# Spannungsteiler_high.net
KiCad netlist of a schematic drawn in Altium Designer
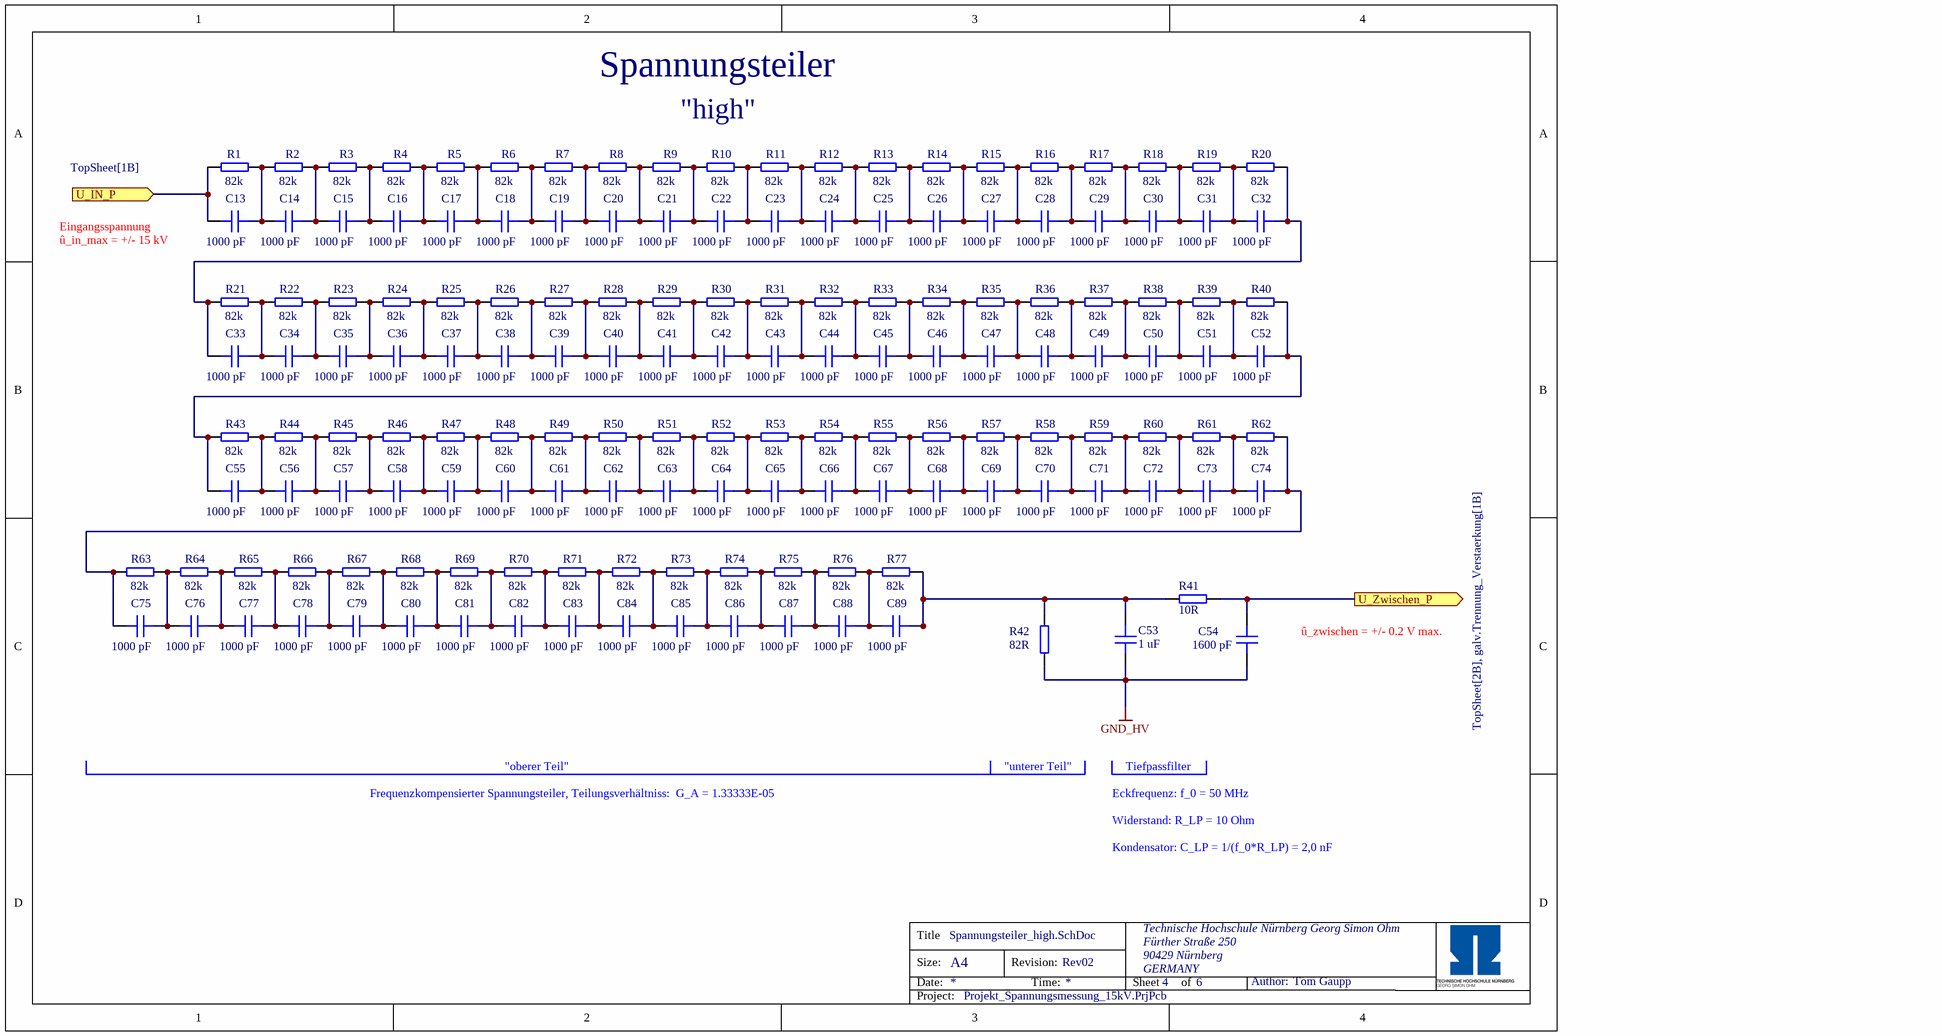
[diagram p0: Spannungsteiler_high.SchDoc]

(export (version "E")
  (design (tool "Eeschema 10.0.6"))
  (components
    (comp (ref "C13")
      (value "1000 pF")
      (footprint "C_1206")
      (description "Capacitor 1206, 200VDC, 1000pF, C0G, 5%")
      (fields
        (field (name "MANUFACTURER") "KEMET")
        (field (name "MANUFACTURER PART NUMBER") "C1206C102J2GACTU")
        (field (name "CREATED FROM") "TGaupp")
      )
      (libsource (lib "user") (part "Capacitor"))
    )
    (comp (ref "C14")
      (value "1000 pF")
      (footprint "C_1206")
      (description "Capacitor 1206, 200VDC, 1000pF, C0G, 5%")
      (fields
        (field (name "MANUFACTURER") "KEMET")
        (field (name "MANUFACTURER PART NUMBER") "C1206C102J2GACTU")
        (field (name "CREATED FROM") "TGaupp")
      )
      (libsource (lib "user") (part "Capacitor"))
    )
    (comp (ref "C15")
      (value "1000 pF")
      (footprint "C_1206")
      (description "Capacitor 1206, 200VDC, 1000pF, C0G, 5%")
      (fields
        (field (name "MANUFACTURER") "KEMET")
        (field (name "MANUFACTURER PART NUMBER") "C1206C102J2GACTU")
        (field (name "CREATED FROM") "TGaupp")
      )
      (libsource (lib "user") (part "Capacitor"))
    )
    (comp (ref "C16")
      (value "1000 pF")
      (footprint "C_1206")
      (description "Capacitor 1206, 200VDC, 1000pF, C0G, 5%")
      (fields
        (field (name "MANUFACTURER") "KEMET")
        (field (name "MANUFACTURER PART NUMBER") "C1206C102J2GACTU")
        (field (name "CREATED FROM") "TGaupp")
      )
      (libsource (lib "user") (part "Capacitor"))
    )
    (comp (ref "C17")
      (value "1000 pF")
      (footprint "C_1206")
      (description "Capacitor 1206, 200VDC, 1000pF, C0G, 5%")
      (fields
        (field (name "MANUFACTURER") "KEMET")
        (field (name "MANUFACTURER PART NUMBER") "C1206C102J2GACTU")
        (field (name "CREATED FROM") "TGaupp")
      )
      (libsource (lib "user") (part "Capacitor"))
    )
    (comp (ref "C18")
      (value "1000 pF")
      (footprint "C_1206")
      (description "Capacitor 1206, 200VDC, 1000pF, C0G, 5%")
      (fields
        (field (name "MANUFACTURER") "KEMET")
        (field (name "MANUFACTURER PART NUMBER") "C1206C102J2GACTU")
        (field (name "CREATED FROM") "TGaupp")
      )
      (libsource (lib "user") (part "Capacitor"))
    )
    (comp (ref "C19")
      (value "1000 pF")
      (footprint "C_1206")
      (description "Capacitor 1206, 200VDC, 1000pF, C0G, 5%")
      (fields
        (field (name "MANUFACTURER") "KEMET")
        (field (name "MANUFACTURER PART NUMBER") "C1206C102J2GACTU")
        (field (name "CREATED FROM") "TGaupp")
      )
      (libsource (lib "user") (part "Capacitor"))
    )
    (comp (ref "C20")
      (value "1000 pF")
      (footprint "C_1206")
      (description "Capacitor 1206, 200VDC, 1000pF, C0G, 5%")
      (fields
        (field (name "MANUFACTURER") "KEMET")
        (field (name "MANUFACTURER PART NUMBER") "C1206C102J2GACTU")
        (field (name "CREATED FROM") "TGaupp")
      )
      (libsource (lib "user") (part "Capacitor"))
    )
    (comp (ref "C21")
      (value "1000 pF")
      (footprint "C_1206")
      (description "Capacitor 1206, 200VDC, 1000pF, C0G, 5%")
      (fields
        (field (name "MANUFACTURER") "KEMET")
        (field (name "MANUFACTURER PART NUMBER") "C1206C102J2GACTU")
        (field (name "CREATED FROM") "TGaupp")
      )
      (libsource (lib "user") (part "Capacitor"))
    )
    (comp (ref "C22")
      (value "1000 pF")
      (footprint "C_1206")
      (description "Capacitor 1206, 200VDC, 1000pF, C0G, 5%")
      (fields
        (field (name "MANUFACTURER") "KEMET")
        (field (name "MANUFACTURER PART NUMBER") "C1206C102J2GACTU")
        (field (name "CREATED FROM") "TGaupp")
      )
      (libsource (lib "user") (part "Capacitor"))
    )
    (comp (ref "C23")
      (value "1000 pF")
      (footprint "C_1206")
      (description "Capacitor 1206, 200VDC, 1000pF, C0G, 5%")
      (fields
        (field (name "MANUFACTURER") "KEMET")
        (field (name "MANUFACTURER PART NUMBER") "C1206C102J2GACTU")
        (field (name "CREATED FROM") "TGaupp")
      )
      (libsource (lib "user") (part "Capacitor"))
    )
    (comp (ref "C24")
      (value "1000 pF")
      (footprint "C_1206")
      (description "Capacitor 1206, 200VDC, 1000pF, C0G, 5%")
      (fields
        (field (name "MANUFACTURER") "KEMET")
        (field (name "MANUFACTURER PART NUMBER") "C1206C102J2GACTU")
        (field (name "CREATED FROM") "TGaupp")
      )
      (libsource (lib "user") (part "Capacitor"))
    )
    (comp (ref "C25")
      (value "1000 pF")
      (footprint "C_1206")
      (description "Capacitor 1206, 200VDC, 1000pF, C0G, 5%")
      (fields
        (field (name "MANUFACTURER") "KEMET")
        (field (name "MANUFACTURER PART NUMBER") "C1206C102J2GACTU")
        (field (name "CREATED FROM") "TGaupp")
      )
      (libsource (lib "user") (part "Capacitor"))
    )
    (comp (ref "C26")
      (value "1000 pF")
      (footprint "C_1206")
      (description "Capacitor 1206, 200VDC, 1000pF, C0G, 5%")
      (fields
        (field (name "MANUFACTURER") "KEMET")
        (field (name "MANUFACTURER PART NUMBER") "C1206C102J2GACTU")
        (field (name "CREATED FROM") "TGaupp")
      )
      (libsource (lib "user") (part "Capacitor"))
    )
    (comp (ref "C27")
      (value "1000 pF")
      (footprint "C_1206")
      (description "Capacitor 1206, 200VDC, 1000pF, C0G, 5%")
      (fields
        (field (name "MANUFACTURER") "KEMET")
        (field (name "MANUFACTURER PART NUMBER") "C1206C102J2GACTU")
        (field (name "CREATED FROM") "TGaupp")
      )
      (libsource (lib "user") (part "Capacitor"))
    )
    (comp (ref "C28")
      (value "1000 pF")
      (footprint "C_1206")
      (description "Capacitor 1206, 200VDC, 1000pF, C0G, 5%")
      (fields
        (field (name "MANUFACTURER") "KEMET")
        (field (name "MANUFACTURER PART NUMBER") "C1206C102J2GACTU")
        (field (name "CREATED FROM") "TGaupp")
      )
      (libsource (lib "user") (part "Capacitor"))
    )
    (comp (ref "C29")
      (value "1000 pF")
      (footprint "C_1206")
      (description "Capacitor 1206, 200VDC, 1000pF, C0G, 5%")
      (fields
        (field (name "MANUFACTURER") "KEMET")
        (field (name "MANUFACTURER PART NUMBER") "C1206C102J2GACTU")
        (field (name "CREATED FROM") "TGaupp")
      )
      (libsource (lib "user") (part "Capacitor"))
    )
    (comp (ref "C30")
      (value "1000 pF")
      (footprint "C_1206")
      (description "Capacitor 1206, 200VDC, 1000pF, C0G, 5%")
      (fields
        (field (name "MANUFACTURER") "KEMET")
        (field (name "MANUFACTURER PART NUMBER") "C1206C102J2GACTU")
        (field (name "CREATED FROM") "TGaupp")
      )
      (libsource (lib "user") (part "Capacitor"))
    )
    (comp (ref "C31")
      (value "1000 pF")
      (footprint "C_1206")
      (description "Capacitor 1206, 200VDC, 1000pF, C0G, 5%")
      (fields
        (field (name "MANUFACTURER") "KEMET")
        (field (name "MANUFACTURER PART NUMBER") "C1206C102J2GACTU")
        (field (name "CREATED FROM") "TGaupp")
      )
      (libsource (lib "user") (part "Capacitor"))
    )
    (comp (ref "C32")
      (value "1000 pF")
      (footprint "C_1206")
      (description "Capacitor 1206, 200VDC, 1000pF, C0G, 5%")
      (fields
        (field (name "MANUFACTURER") "KEMET")
        (field (name "MANUFACTURER PART NUMBER") "C1206C102J2GACTU")
        (field (name "CREATED FROM") "TGaupp")
      )
      (libsource (lib "user") (part "Capacitor"))
    )
    (comp (ref "C33")
      (value "1000 pF")
      (footprint "C_1206")
      (description "Capacitor 1206, 200VDC, 1000pF, C0G, 5%")
      (fields
        (field (name "MANUFACTURER") "KEMET")
        (field (name "MANUFACTURER PART NUMBER") "C1206C102J2GACTU")
        (field (name "CREATED FROM") "TGaupp")
      )
      (libsource (lib "user") (part "Capacitor"))
    )
    (comp (ref "C34")
      (value "1000 pF")
      (footprint "C_1206")
      (description "Capacitor 1206, 200VDC, 1000pF, C0G, 5%")
      (fields
        (field (name "MANUFACTURER") "KEMET")
        (field (name "MANUFACTURER PART NUMBER") "C1206C102J2GACTU")
        (field (name "CREATED FROM") "TGaupp")
      )
      (libsource (lib "user") (part "Capacitor"))
    )
    (comp (ref "C35")
      (value "1000 pF")
      (footprint "C_1206")
      (description "Capacitor 1206, 200VDC, 1000pF, C0G, 5%")
      (fields
        (field (name "MANUFACTURER") "KEMET")
        (field (name "MANUFACTURER PART NUMBER") "C1206C102J2GACTU")
        (field (name "CREATED FROM") "TGaupp")
      )
      (libsource (lib "user") (part "Capacitor"))
    )
    (comp (ref "C36")
      (value "1000 pF")
      (footprint "C_1206")
      (description "Capacitor 1206, 200VDC, 1000pF, C0G, 5%")
      (fields
        (field (name "MANUFACTURER") "KEMET")
        (field (name "MANUFACTURER PART NUMBER") "C1206C102J2GACTU")
        (field (name "CREATED FROM") "TGaupp")
      )
      (libsource (lib "user") (part "Capacitor"))
    )
    (comp (ref "C37")
      (value "1000 pF")
      (footprint "C_1206")
      (description "Capacitor 1206, 200VDC, 1000pF, C0G, 5%")
      (fields
        (field (name "MANUFACTURER") "KEMET")
        (field (name "MANUFACTURER PART NUMBER") "C1206C102J2GACTU")
        (field (name "CREATED FROM") "TGaupp")
      )
      (libsource (lib "user") (part "Capacitor"))
    )
    (comp (ref "C38")
      (value "1000 pF")
      (footprint "C_1206")
      (description "Capacitor 1206, 200VDC, 1000pF, C0G, 5%")
      (fields
        (field (name "MANUFACTURER") "KEMET")
        (field (name "MANUFACTURER PART NUMBER") "C1206C102J2GACTU")
        (field (name "CREATED FROM") "TGaupp")
      )
      (libsource (lib "user") (part "Capacitor"))
    )
    (comp (ref "C39")
      (value "1000 pF")
      (footprint "C_1206")
      (description "Capacitor 1206, 200VDC, 1000pF, C0G, 5%")
      (fields
        (field (name "MANUFACTURER") "KEMET")
        (field (name "MANUFACTURER PART NUMBER") "C1206C102J2GACTU")
        (field (name "CREATED FROM") "TGaupp")
      )
      (libsource (lib "user") (part "Capacitor"))
    )
    (comp (ref "C40")
      (value "1000 pF")
      (footprint "C_1206")
      (description "Capacitor 1206, 200VDC, 1000pF, C0G, 5%")
      (fields
        (field (name "MANUFACTURER") "KEMET")
        (field (name "MANUFACTURER PART NUMBER") "C1206C102J2GACTU")
        (field (name "CREATED FROM") "TGaupp")
      )
      (libsource (lib "user") (part "Capacitor"))
    )
    (comp (ref "C41")
      (value "1000 pF")
      (footprint "C_1206")
      (description "Capacitor 1206, 200VDC, 1000pF, C0G, 5%")
      (fields
        (field (name "MANUFACTURER") "KEMET")
        (field (name "MANUFACTURER PART NUMBER") "C1206C102J2GACTU")
        (field (name "CREATED FROM") "TGaupp")
      )
      (libsource (lib "user") (part "Capacitor"))
    )
    (comp (ref "C42")
      (value "1000 pF")
      (footprint "C_1206")
      (description "Capacitor 1206, 200VDC, 1000pF, C0G, 5%")
      (fields
        (field (name "MANUFACTURER") "KEMET")
        (field (name "MANUFACTURER PART NUMBER") "C1206C102J2GACTU")
        (field (name "CREATED FROM") "TGaupp")
      )
      (libsource (lib "user") (part "Capacitor"))
    )
    (comp (ref "C43")
      (value "1000 pF")
      (footprint "C_1206")
      (description "Capacitor 1206, 200VDC, 1000pF, C0G, 5%")
      (fields
        (field (name "MANUFACTURER") "KEMET")
        (field (name "MANUFACTURER PART NUMBER") "C1206C102J2GACTU")
        (field (name "CREATED FROM") "TGaupp")
      )
      (libsource (lib "user") (part "Capacitor"))
    )
    (comp (ref "C44")
      (value "1000 pF")
      (footprint "C_1206")
      (description "Capacitor 1206, 200VDC, 1000pF, C0G, 5%")
      (fields
        (field (name "MANUFACTURER") "KEMET")
        (field (name "MANUFACTURER PART NUMBER") "C1206C102J2GACTU")
        (field (name "CREATED FROM") "TGaupp")
      )
      (libsource (lib "user") (part "Capacitor"))
    )
    (comp (ref "C45")
      (value "1000 pF")
      (footprint "C_1206")
      (description "Capacitor 1206, 200VDC, 1000pF, C0G, 5%")
      (fields
        (field (name "MANUFACTURER") "KEMET")
        (field (name "MANUFACTURER PART NUMBER") "C1206C102J2GACTU")
        (field (name "CREATED FROM") "TGaupp")
      )
      (libsource (lib "user") (part "Capacitor"))
    )
    (comp (ref "C46")
      (value "1000 pF")
      (footprint "C_1206")
      (description "Capacitor 1206, 200VDC, 1000pF, C0G, 5%")
      (fields
        (field (name "MANUFACTURER") "KEMET")
        (field (name "MANUFACTURER PART NUMBER") "C1206C102J2GACTU")
        (field (name "CREATED FROM") "TGaupp")
      )
      (libsource (lib "user") (part "Capacitor"))
    )
    (comp (ref "C47")
      (value "1000 pF")
      (footprint "C_1206")
      (description "Capacitor 1206, 200VDC, 1000pF, C0G, 5%")
      (fields
        (field (name "MANUFACTURER") "KEMET")
        (field (name "MANUFACTURER PART NUMBER") "C1206C102J2GACTU")
        (field (name "CREATED FROM") "TGaupp")
      )
      (libsource (lib "user") (part "Capacitor"))
    )
    (comp (ref "C48")
      (value "1000 pF")
      (footprint "C_1206")
      (description "Capacitor 1206, 200VDC, 1000pF, C0G, 5%")
      (fields
        (field (name "MANUFACTURER") "KEMET")
        (field (name "MANUFACTURER PART NUMBER") "C1206C102J2GACTU")
        (field (name "CREATED FROM") "TGaupp")
      )
      (libsource (lib "user") (part "Capacitor"))
    )
    (comp (ref "C49")
      (value "1000 pF")
      (footprint "C_1206")
      (description "Capacitor 1206, 200VDC, 1000pF, C0G, 5%")
      (fields
        (field (name "MANUFACTURER") "KEMET")
        (field (name "MANUFACTURER PART NUMBER") "C1206C102J2GACTU")
        (field (name "CREATED FROM") "TGaupp")
      )
      (libsource (lib "user") (part "Capacitor"))
    )
    (comp (ref "C50")
      (value "1000 pF")
      (footprint "C_1206")
      (description "Capacitor 1206, 200VDC, 1000pF, C0G, 5%")
      (fields
        (field (name "MANUFACTURER") "KEMET")
        (field (name "MANUFACTURER PART NUMBER") "C1206C102J2GACTU")
        (field (name "CREATED FROM") "TGaupp")
      )
      (libsource (lib "user") (part "Capacitor"))
    )
    (comp (ref "C51")
      (value "1000 pF")
      (footprint "C_1206")
      (description "Capacitor 1206, 200VDC, 1000pF, C0G, 5%")
      (fields
        (field (name "MANUFACTURER") "KEMET")
        (field (name "MANUFACTURER PART NUMBER") "C1206C102J2GACTU")
        (field (name "CREATED FROM") "TGaupp")
      )
      (libsource (lib "user") (part "Capacitor"))
    )
    (comp (ref "C52")
      (value "1000 pF")
      (footprint "C_1206")
      (description "Capacitor 1206, 200VDC, 1000pF, C0G, 5%")
      (fields
        (field (name "MANUFACTURER") "KEMET")
        (field (name "MANUFACTURER PART NUMBER") "C1206C102J2GACTU")
        (field (name "CREATED FROM") "TGaupp")
      )
      (libsource (lib "user") (part "Capacitor"))
    )
    (comp (ref "C53")
      (value "1 uF")
      (footprint "C_1206")
      (description "Capacitor 1206, 50V, 1uF, X7R, 5%")
      (fields
        (field (name "MANUFACTURER PART NUMBER") "C1206X105J5RACTU")
        (field (name "MANUFACTURER") "KEMET")
        (field (name "CREATED FROM") "TGaupp")
      )
      (libsource (lib "user") (part "Capacitor"))
    )
    (comp (ref "C54")
      (value "1600 pF")
      (footprint "C_1206")
      (description "Capacitor 1206, 25V, 1600pF, X8R, 10%")
      (fields
        (field (name "MANUFACTURER") "KEMET")
        (field (name "MANUFACTURER PART NUMBER") "C1206C162K3HACTU")
        (field (name "CREATED FROM") "TGaupp")
      )
      (libsource (lib "user") (part "Capacitor"))
    )
    (comp (ref "C55")
      (value "1000 pF")
      (footprint "C_1206")
      (description "Capacitor 1206, 200VDC, 1000pF, C0G, 5%")
      (fields
        (field (name "MANUFACTURER") "KEMET")
        (field (name "MANUFACTURER PART NUMBER") "C1206C102J2GACTU")
        (field (name "CREATED FROM") "TGaupp")
      )
      (libsource (lib "user") (part "Capacitor"))
    )
    (comp (ref "C56")
      (value "1000 pF")
      (footprint "C_1206")
      (description "Capacitor 1206, 200VDC, 1000pF, C0G, 5%")
      (fields
        (field (name "MANUFACTURER") "KEMET")
        (field (name "MANUFACTURER PART NUMBER") "C1206C102J2GACTU")
        (field (name "CREATED FROM") "TGaupp")
      )
      (libsource (lib "user") (part "Capacitor"))
    )
    (comp (ref "C57")
      (value "1000 pF")
      (footprint "C_1206")
      (description "Capacitor 1206, 200VDC, 1000pF, C0G, 5%")
      (fields
        (field (name "MANUFACTURER") "KEMET")
        (field (name "MANUFACTURER PART NUMBER") "C1206C102J2GACTU")
        (field (name "CREATED FROM") "TGaupp")
      )
      (libsource (lib "user") (part "Capacitor"))
    )
    (comp (ref "C58")
      (value "1000 pF")
      (footprint "C_1206")
      (description "Capacitor 1206, 200VDC, 1000pF, C0G, 5%")
      (fields
        (field (name "MANUFACTURER") "KEMET")
        (field (name "MANUFACTURER PART NUMBER") "C1206C102J2GACTU")
        (field (name "CREATED FROM") "TGaupp")
      )
      (libsource (lib "user") (part "Capacitor"))
    )
    (comp (ref "C59")
      (value "1000 pF")
      (footprint "C_1206")
      (description "Capacitor 1206, 200VDC, 1000pF, C0G, 5%")
      (fields
        (field (name "MANUFACTURER") "KEMET")
        (field (name "MANUFACTURER PART NUMBER") "C1206C102J2GACTU")
        (field (name "CREATED FROM") "TGaupp")
      )
      (libsource (lib "user") (part "Capacitor"))
    )
    (comp (ref "C60")
      (value "1000 pF")
      (footprint "C_1206")
      (description "Capacitor 1206, 200VDC, 1000pF, C0G, 5%")
      (fields
        (field (name "MANUFACTURER") "KEMET")
        (field (name "MANUFACTURER PART NUMBER") "C1206C102J2GACTU")
        (field (name "CREATED FROM") "TGaupp")
      )
      (libsource (lib "user") (part "Capacitor"))
    )
    (comp (ref "C61")
      (value "1000 pF")
      (footprint "C_1206")
      (description "Capacitor 1206, 200VDC, 1000pF, C0G, 5%")
      (fields
        (field (name "MANUFACTURER") "KEMET")
        (field (name "MANUFACTURER PART NUMBER") "C1206C102J2GACTU")
        (field (name "CREATED FROM") "TGaupp")
      )
      (libsource (lib "user") (part "Capacitor"))
    )
    (comp (ref "C62")
      (value "1000 pF")
      (footprint "C_1206")
      (description "Capacitor 1206, 200VDC, 1000pF, C0G, 5%")
      (fields
        (field (name "MANUFACTURER") "KEMET")
        (field (name "MANUFACTURER PART NUMBER") "C1206C102J2GACTU")
        (field (name "CREATED FROM") "TGaupp")
      )
      (libsource (lib "user") (part "Capacitor"))
    )
    (comp (ref "C63")
      (value "1000 pF")
      (footprint "C_1206")
      (description "Capacitor 1206, 200VDC, 1000pF, C0G, 5%")
      (fields
        (field (name "MANUFACTURER") "KEMET")
        (field (name "MANUFACTURER PART NUMBER") "C1206C102J2GACTU")
        (field (name "CREATED FROM") "TGaupp")
      )
      (libsource (lib "user") (part "Capacitor"))
    )
    (comp (ref "C64")
      (value "1000 pF")
      (footprint "C_1206")
      (description "Capacitor 1206, 200VDC, 1000pF, C0G, 5%")
      (fields
        (field (name "MANUFACTURER") "KEMET")
        (field (name "MANUFACTURER PART NUMBER") "C1206C102J2GACTU")
        (field (name "CREATED FROM") "TGaupp")
      )
      (libsource (lib "user") (part "Capacitor"))
    )
    (comp (ref "C65")
      (value "1000 pF")
      (footprint "C_1206")
      (description "Capacitor 1206, 200VDC, 1000pF, C0G, 5%")
      (fields
        (field (name "MANUFACTURER") "KEMET")
        (field (name "MANUFACTURER PART NUMBER") "C1206C102J2GACTU")
        (field (name "CREATED FROM") "TGaupp")
      )
      (libsource (lib "user") (part "Capacitor"))
    )
    (comp (ref "C66")
      (value "1000 pF")
      (footprint "C_1206")
      (description "Capacitor 1206, 200VDC, 1000pF, C0G, 5%")
      (fields
        (field (name "MANUFACTURER") "KEMET")
        (field (name "MANUFACTURER PART NUMBER") "C1206C102J2GACTU")
        (field (name "CREATED FROM") "TGaupp")
      )
      (libsource (lib "user") (part "Capacitor"))
    )
    (comp (ref "C67")
      (value "1000 pF")
      (footprint "C_1206")
      (description "Capacitor 1206, 200VDC, 1000pF, C0G, 5%")
      (fields
        (field (name "MANUFACTURER") "KEMET")
        (field (name "MANUFACTURER PART NUMBER") "C1206C102J2GACTU")
        (field (name "CREATED FROM") "TGaupp")
      )
      (libsource (lib "user") (part "Capacitor"))
    )
    (comp (ref "C68")
      (value "1000 pF")
      (footprint "C_1206")
      (description "Capacitor 1206, 200VDC, 1000pF, C0G, 5%")
      (fields
        (field (name "MANUFACTURER") "KEMET")
        (field (name "MANUFACTURER PART NUMBER") "C1206C102J2GACTU")
        (field (name "CREATED FROM") "TGaupp")
      )
      (libsource (lib "user") (part "Capacitor"))
    )
    (comp (ref "C69")
      (value "1000 pF")
      (footprint "C_1206")
      (description "Capacitor 1206, 200VDC, 1000pF, C0G, 5%")
      (fields
        (field (name "MANUFACTURER") "KEMET")
        (field (name "MANUFACTURER PART NUMBER") "C1206C102J2GACTU")
        (field (name "CREATED FROM") "TGaupp")
      )
      (libsource (lib "user") (part "Capacitor"))
    )
    (comp (ref "C70")
      (value "1000 pF")
      (footprint "C_1206")
      (description "Capacitor 1206, 200VDC, 1000pF, C0G, 5%")
      (fields
        (field (name "MANUFACTURER") "KEMET")
        (field (name "MANUFACTURER PART NUMBER") "C1206C102J2GACTU")
        (field (name "CREATED FROM") "TGaupp")
      )
      (libsource (lib "user") (part "Capacitor"))
    )
    (comp (ref "C71")
      (value "1000 pF")
      (footprint "C_1206")
      (description "Capacitor 1206, 200VDC, 1000pF, C0G, 5%")
      (fields
        (field (name "MANUFACTURER") "KEMET")
        (field (name "MANUFACTURER PART NUMBER") "C1206C102J2GACTU")
        (field (name "CREATED FROM") "TGaupp")
      )
      (libsource (lib "user") (part "Capacitor"))
    )
    (comp (ref "C72")
      (value "1000 pF")
      (footprint "C_1206")
      (description "Capacitor 1206, 200VDC, 1000pF, C0G, 5%")
      (fields
        (field (name "MANUFACTURER") "KEMET")
        (field (name "MANUFACTURER PART NUMBER") "C1206C102J2GACTU")
        (field (name "CREATED FROM") "TGaupp")
      )
      (libsource (lib "user") (part "Capacitor"))
    )
    (comp (ref "C73")
      (value "1000 pF")
      (footprint "C_1206")
      (description "Capacitor 1206, 200VDC, 1000pF, C0G, 5%")
      (fields
        (field (name "MANUFACTURER") "KEMET")
        (field (name "MANUFACTURER PART NUMBER") "C1206C102J2GACTU")
        (field (name "CREATED FROM") "TGaupp")
      )
      (libsource (lib "user") (part "Capacitor"))
    )
    (comp (ref "C74")
      (value "1000 pF")
      (footprint "C_1206")
      (description "Capacitor 1206, 200VDC, 1000pF, C0G, 5%")
      (fields
        (field (name "MANUFACTURER") "KEMET")
        (field (name "MANUFACTURER PART NUMBER") "C1206C102J2GACTU")
        (field (name "CREATED FROM") "TGaupp")
      )
      (libsource (lib "user") (part "Capacitor"))
    )
    (comp (ref "C75")
      (value "1000 pF")
      (footprint "C_1206")
      (description "Capacitor 1206, 200VDC, 1000pF, C0G, 5%")
      (fields
        (field (name "MANUFACTURER") "KEMET")
        (field (name "MANUFACTURER PART NUMBER") "C1206C102J2GACTU")
        (field (name "CREATED FROM") "TGaupp")
      )
      (libsource (lib "user") (part "Capacitor"))
    )
    (comp (ref "C76")
      (value "1000 pF")
      (footprint "C_1206")
      (description "Capacitor 1206, 200VDC, 1000pF, C0G, 5%")
      (fields
        (field (name "MANUFACTURER") "KEMET")
        (field (name "MANUFACTURER PART NUMBER") "C1206C102J2GACTU")
        (field (name "CREATED FROM") "TGaupp")
      )
      (libsource (lib "user") (part "Capacitor"))
    )
    (comp (ref "C77")
      (value "1000 pF")
      (footprint "C_1206")
      (description "Capacitor 1206, 200VDC, 1000pF, C0G, 5%")
      (fields
        (field (name "MANUFACTURER") "KEMET")
        (field (name "MANUFACTURER PART NUMBER") "C1206C102J2GACTU")
        (field (name "CREATED FROM") "TGaupp")
      )
      (libsource (lib "user") (part "Capacitor"))
    )
    (comp (ref "C78")
      (value "1000 pF")
      (footprint "C_1206")
      (description "Capacitor 1206, 200VDC, 1000pF, C0G, 5%")
      (fields
        (field (name "MANUFACTURER") "KEMET")
        (field (name "MANUFACTURER PART NUMBER") "C1206C102J2GACTU")
        (field (name "CREATED FROM") "TGaupp")
      )
      (libsource (lib "user") (part "Capacitor"))
    )
    (comp (ref "C79")
      (value "1000 pF")
      (footprint "C_1206")
      (description "Capacitor 1206, 200VDC, 1000pF, C0G, 5%")
      (fields
        (field (name "MANUFACTURER") "KEMET")
        (field (name "MANUFACTURER PART NUMBER") "C1206C102J2GACTU")
        (field (name "CREATED FROM") "TGaupp")
      )
      (libsource (lib "user") (part "Capacitor"))
    )
    (comp (ref "C80")
      (value "1000 pF")
      (footprint "C_1206")
      (description "Capacitor 1206, 200VDC, 1000pF, C0G, 5%")
      (fields
        (field (name "MANUFACTURER") "KEMET")
        (field (name "MANUFACTURER PART NUMBER") "C1206C102J2GACTU")
        (field (name "CREATED FROM") "TGaupp")
      )
      (libsource (lib "user") (part "Capacitor"))
    )
    (comp (ref "C81")
      (value "1000 pF")
      (footprint "C_1206")
      (description "Capacitor 1206, 200VDC, 1000pF, C0G, 5%")
      (fields
        (field (name "MANUFACTURER") "KEMET")
        (field (name "MANUFACTURER PART NUMBER") "C1206C102J2GACTU")
        (field (name "CREATED FROM") "TGaupp")
      )
      (libsource (lib "user") (part "Capacitor"))
    )
    (comp (ref "C82")
      (value "1000 pF")
      (footprint "C_1206")
      (description "Capacitor 1206, 200VDC, 1000pF, C0G, 5%")
      (fields
        (field (name "MANUFACTURER") "KEMET")
        (field (name "MANUFACTURER PART NUMBER") "C1206C102J2GACTU")
        (field (name "CREATED FROM") "TGaupp")
      )
      (libsource (lib "user") (part "Capacitor"))
    )
    (comp (ref "C83")
      (value "1000 pF")
      (footprint "C_1206")
      (description "Capacitor 1206, 200VDC, 1000pF, C0G, 5%")
      (fields
        (field (name "MANUFACTURER") "KEMET")
        (field (name "MANUFACTURER PART NUMBER") "C1206C102J2GACTU")
        (field (name "CREATED FROM") "TGaupp")
      )
      (libsource (lib "user") (part "Capacitor"))
    )
    (comp (ref "C84")
      (value "1000 pF")
      (footprint "C_1206")
      (description "Capacitor 1206, 200VDC, 1000pF, C0G, 5%")
      (fields
        (field (name "MANUFACTURER") "KEMET")
        (field (name "MANUFACTURER PART NUMBER") "C1206C102J2GACTU")
        (field (name "CREATED FROM") "TGaupp")
      )
      (libsource (lib "user") (part "Capacitor"))
    )
    (comp (ref "C85")
      (value "1000 pF")
      (footprint "C_1206")
      (description "Capacitor 1206, 200VDC, 1000pF, C0G, 5%")
      (fields
        (field (name "MANUFACTURER") "KEMET")
        (field (name "MANUFACTURER PART NUMBER") "C1206C102J2GACTU")
        (field (name "CREATED FROM") "TGaupp")
      )
      (libsource (lib "user") (part "Capacitor"))
    )
    (comp (ref "C86")
      (value "1000 pF")
      (footprint "C_1206")
      (description "Capacitor 1206, 200VDC, 1000pF, C0G, 5%")
      (fields
        (field (name "MANUFACTURER") "KEMET")
        (field (name "MANUFACTURER PART NUMBER") "C1206C102J2GACTU")
        (field (name "CREATED FROM") "TGaupp")
      )
      (libsource (lib "user") (part "Capacitor"))
    )
    (comp (ref "C87")
      (value "1000 pF")
      (footprint "C_1206")
      (description "Capacitor 1206, 200VDC, 1000pF, C0G, 5%")
      (fields
        (field (name "MANUFACTURER") "KEMET")
        (field (name "MANUFACTURER PART NUMBER") "C1206C102J2GACTU")
        (field (name "CREATED FROM") "TGaupp")
      )
      (libsource (lib "user") (part "Capacitor"))
    )
    (comp (ref "C88")
      (value "1000 pF")
      (footprint "C_1206")
      (description "Capacitor 1206, 200VDC, 1000pF, C0G, 5%")
      (fields
        (field (name "MANUFACTURER") "KEMET")
        (field (name "MANUFACTURER PART NUMBER") "C1206C102J2GACTU")
        (field (name "CREATED FROM") "TGaupp")
      )
      (libsource (lib "user") (part "Capacitor"))
    )
    (comp (ref "C89")
      (value "1000 pF")
      (footprint "C_1206")
      (description "Capacitor 1206, 200VDC, 1000pF, C0G, 5%")
      (fields
        (field (name "MANUFACTURER") "KEMET")
        (field (name "MANUFACTURER PART NUMBER") "C1206C102J2GACTU")
        (field (name "CREATED FROM") "TGaupp")
      )
      (libsource (lib "user") (part "Capacitor"))
    )
    (comp (ref "R1")
      (value "82k")
      (footprint "RES 1206_3216")
      (description "SMD resistor 82Kohms .1% 25ppm")
      (fields
        (field (name "MANUFACTURER") "Vishay")
        (field (name "MANUFACTURER PART NUMBER") "TNPW120682K0BEEA")
        (field (name "CREATED FROM") "TGaupp")
      )
      (libsource (lib "user") (part "Resistor"))
    )
    (comp (ref "R2")
      (value "82k")
      (footprint "RES 1206_3216")
      (description "SMD resistor 82Kohms .1% 25ppm")
      (fields
        (field (name "MANUFACTURER") "Vishay")
        (field (name "MANUFACTURER PART NUMBER") "TNPW120682K0BEEA")
        (field (name "CREATED FROM") "TGaupp")
      )
      (libsource (lib "user") (part "Resistor"))
    )
    (comp (ref "R3")
      (value "82k")
      (footprint "RES 1206_3216")
      (description "SMD resistor 82Kohms .1% 25ppm")
      (fields
        (field (name "MANUFACTURER") "Vishay")
        (field (name "MANUFACTURER PART NUMBER") "TNPW120682K0BEEA")
        (field (name "CREATED FROM") "TGaupp")
      )
      (libsource (lib "user") (part "Resistor"))
    )
    (comp (ref "R4")
      (value "82k")
      (footprint "RES 1206_3216")
      (description "SMD resistor 82Kohms .1% 25ppm")
      (fields
        (field (name "MANUFACTURER") "Vishay")
        (field (name "MANUFACTURER PART NUMBER") "TNPW120682K0BEEA")
        (field (name "CREATED FROM") "TGaupp")
      )
      (libsource (lib "user") (part "Resistor"))
    )
    (comp (ref "R5")
      (value "82k")
      (footprint "RES 1206_3216")
      (description "SMD resistor 82Kohms .1% 25ppm")
      (fields
        (field (name "MANUFACTURER") "Vishay")
        (field (name "MANUFACTURER PART NUMBER") "TNPW120682K0BEEA")
        (field (name "CREATED FROM") "TGaupp")
      )
      (libsource (lib "user") (part "Resistor"))
    )
    (comp (ref "R6")
      (value "82k")
      (footprint "RES 1206_3216")
      (description "SMD resistor 82Kohms .1% 25ppm")
      (fields
        (field (name "MANUFACTURER") "Vishay")
        (field (name "MANUFACTURER PART NUMBER") "TNPW120682K0BEEA")
        (field (name "CREATED FROM") "TGaupp")
      )
      (libsource (lib "user") (part "Resistor"))
    )
    (comp (ref "R7")
      (value "82k")
      (footprint "RES 1206_3216")
      (description "SMD resistor 82Kohms .1% 25ppm")
      (fields
        (field (name "MANUFACTURER") "Vishay")
        (field (name "MANUFACTURER PART NUMBER") "TNPW120682K0BEEA")
        (field (name "CREATED FROM") "TGaupp")
      )
      (libsource (lib "user") (part "Resistor"))
    )
    (comp (ref "R8")
      (value "82k")
      (footprint "RES 1206_3216")
      (description "SMD resistor 82Kohms .1% 25ppm")
      (fields
        (field (name "MANUFACTURER") "Vishay")
        (field (name "MANUFACTURER PART NUMBER") "TNPW120682K0BEEA")
        (field (name "CREATED FROM") "TGaupp")
      )
      (libsource (lib "user") (part "Resistor"))
    )
    (comp (ref "R9")
      (value "82k")
      (footprint "RES 1206_3216")
      (description "SMD resistor 82Kohms .1% 25ppm")
      (fields
        (field (name "MANUFACTURER") "Vishay")
        (field (name "MANUFACTURER PART NUMBER") "TNPW120682K0BEEA")
        (field (name "CREATED FROM") "TGaupp")
      )
      (libsource (lib "user") (part "Resistor"))
    )
    (comp (ref "R10")
      (value "82k")
      (footprint "RES 1206_3216")
      (description "SMD resistor 82Kohms .1% 25ppm")
      (fields
        (field (name "MANUFACTURER") "Vishay")
        (field (name "MANUFACTURER PART NUMBER") "TNPW120682K0BEEA")
        (field (name "CREATED FROM") "TGaupp")
      )
      (libsource (lib "user") (part "Resistor"))
    )
    (comp (ref "R11")
      (value "82k")
      (footprint "RES 1206_3216")
      (description "SMD resistor 82Kohms .1% 25ppm")
      (fields
        (field (name "MANUFACTURER") "Vishay")
        (field (name "MANUFACTURER PART NUMBER") "TNPW120682K0BEEA")
        (field (name "CREATED FROM") "TGaupp")
      )
      (libsource (lib "user") (part "Resistor"))
    )
    (comp (ref "R12")
      (value "82k")
      (footprint "RES 1206_3216")
      (description "SMD resistor 82Kohms .1% 25ppm")
      (fields
        (field (name "MANUFACTURER") "Vishay")
        (field (name "MANUFACTURER PART NUMBER") "TNPW120682K0BEEA")
        (field (name "CREATED FROM") "TGaupp")
      )
      (libsource (lib "user") (part "Resistor"))
    )
    (comp (ref "R13")
      (value "82k")
      (footprint "RES 1206_3216")
      (description "SMD resistor 82Kohms .1% 25ppm")
      (fields
        (field (name "MANUFACTURER") "Vishay")
        (field (name "MANUFACTURER PART NUMBER") "TNPW120682K0BEEA")
        (field (name "CREATED FROM") "TGaupp")
      )
      (libsource (lib "user") (part "Resistor"))
    )
    (comp (ref "R14")
      (value "82k")
      (footprint "RES 1206_3216")
      (description "SMD resistor 82Kohms .1% 25ppm")
      (fields
        (field (name "MANUFACTURER") "Vishay")
        (field (name "MANUFACTURER PART NUMBER") "TNPW120682K0BEEA")
        (field (name "CREATED FROM") "TGaupp")
      )
      (libsource (lib "user") (part "Resistor"))
    )
    (comp (ref "R15")
      (value "82k")
      (footprint "RES 1206_3216")
      (description "SMD resistor 82Kohms .1% 25ppm")
      (fields
        (field (name "MANUFACTURER") "Vishay")
        (field (name "MANUFACTURER PART NUMBER") "TNPW120682K0BEEA")
        (field (name "CREATED FROM") "TGaupp")
      )
      (libsource (lib "user") (part "Resistor"))
    )
    (comp (ref "R16")
      (value "82k")
      (footprint "RES 1206_3216")
      (description "SMD resistor 82Kohms .1% 25ppm")
      (fields
        (field (name "MANUFACTURER") "Vishay")
        (field (name "MANUFACTURER PART NUMBER") "TNPW120682K0BEEA")
        (field (name "CREATED FROM") "TGaupp")
      )
      (libsource (lib "user") (part "Resistor"))
    )
    (comp (ref "R17")
      (value "82k")
      (footprint "RES 1206_3216")
      (description "SMD resistor 82Kohms .1% 25ppm")
      (fields
        (field (name "MANUFACTURER") "Vishay")
        (field (name "MANUFACTURER PART NUMBER") "TNPW120682K0BEEA")
        (field (name "CREATED FROM") "TGaupp")
      )
      (libsource (lib "user") (part "Resistor"))
    )
    (comp (ref "R18")
      (value "82k")
      (footprint "RES 1206_3216")
      (description "SMD resistor 82Kohms .1% 25ppm")
      (fields
        (field (name "MANUFACTURER") "Vishay")
        (field (name "MANUFACTURER PART NUMBER") "TNPW120682K0BEEA")
        (field (name "CREATED FROM") "TGaupp")
      )
      (libsource (lib "user") (part "Resistor"))
    )
    (comp (ref "R19")
      (value "82k")
      (footprint "RES 1206_3216")
      (description "SMD resistor 82Kohms .1% 25ppm")
      (fields
        (field (name "MANUFACTURER") "Vishay")
        (field (name "MANUFACTURER PART NUMBER") "TNPW120682K0BEEA")
        (field (name "CREATED FROM") "TGaupp")
      )
      (libsource (lib "user") (part "Resistor"))
    )
    (comp (ref "R20")
      (value "82k")
      (footprint "RES 1206_3216")
      (description "SMD resistor 82Kohms .1% 25ppm")
      (fields
        (field (name "MANUFACTURER") "Vishay")
        (field (name "MANUFACTURER PART NUMBER") "TNPW120682K0BEEA")
        (field (name "CREATED FROM") "TGaupp")
      )
      (libsource (lib "user") (part "Resistor"))
    )
    (comp (ref "R21")
      (value "82k")
      (footprint "RES 1206_3216")
      (description "SMD resistor 82Kohms .1% 25ppm")
      (fields
        (field (name "MANUFACTURER") "Vishay")
        (field (name "MANUFACTURER PART NUMBER") "TNPW120682K0BEEA")
        (field (name "CREATED FROM") "TGaupp")
      )
      (libsource (lib "user") (part "Resistor"))
    )
    (comp (ref "R22")
      (value "82k")
      (footprint "RES 1206_3216")
      (description "SMD resistor 82Kohms .1% 25ppm")
      (fields
        (field (name "MANUFACTURER") "Vishay")
        (field (name "MANUFACTURER PART NUMBER") "TNPW120682K0BEEA")
        (field (name "CREATED FROM") "TGaupp")
      )
      (libsource (lib "user") (part "Resistor"))
    )
    (comp (ref "R23")
      (value "82k")
      (footprint "RES 1206_3216")
      (description "SMD resistor 82Kohms .1% 25ppm")
      (fields
        (field (name "MANUFACTURER") "Vishay")
        (field (name "MANUFACTURER PART NUMBER") "TNPW120682K0BEEA")
        (field (name "CREATED FROM") "TGaupp")
      )
      (libsource (lib "user") (part "Resistor"))
    )
    (comp (ref "R24")
      (value "82k")
      (footprint "RES 1206_3216")
      (description "SMD resistor 82Kohms .1% 25ppm")
      (fields
        (field (name "MANUFACTURER") "Vishay")
        (field (name "MANUFACTURER PART NUMBER") "TNPW120682K0BEEA")
        (field (name "CREATED FROM") "TGaupp")
      )
      (libsource (lib "user") (part "Resistor"))
    )
    (comp (ref "R25")
      (value "82k")
      (footprint "RES 1206_3216")
      (description "SMD resistor 82Kohms .1% 25ppm")
      (fields
        (field (name "MANUFACTURER") "Vishay")
        (field (name "MANUFACTURER PART NUMBER") "TNPW120682K0BEEA")
        (field (name "CREATED FROM") "TGaupp")
      )
      (libsource (lib "user") (part "Resistor"))
    )
    (comp (ref "R26")
      (value "82k")
      (footprint "RES 1206_3216")
      (description "SMD resistor 82Kohms .1% 25ppm")
      (fields
        (field (name "MANUFACTURER") "Vishay")
        (field (name "MANUFACTURER PART NUMBER") "TNPW120682K0BEEA")
        (field (name "CREATED FROM") "TGaupp")
      )
      (libsource (lib "user") (part "Resistor"))
    )
    (comp (ref "R27")
      (value "82k")
      (footprint "RES 1206_3216")
      (description "SMD resistor 82Kohms .1% 25ppm")
      (fields
        (field (name "MANUFACTURER") "Vishay")
        (field (name "MANUFACTURER PART NUMBER") "TNPW120682K0BEEA")
        (field (name "CREATED FROM") "TGaupp")
      )
      (libsource (lib "user") (part "Resistor"))
    )
    (comp (ref "R28")
      (value "82k")
      (footprint "RES 1206_3216")
      (description "SMD resistor 82Kohms .1% 25ppm")
      (fields
        (field (name "MANUFACTURER") "Vishay")
        (field (name "MANUFACTURER PART NUMBER") "TNPW120682K0BEEA")
        (field (name "CREATED FROM") "TGaupp")
      )
      (libsource (lib "user") (part "Resistor"))
    )
    (comp (ref "R29")
      (value "82k")
      (footprint "RES 1206_3216")
      (description "SMD resistor 82Kohms .1% 25ppm")
      (fields
        (field (name "MANUFACTURER") "Vishay")
        (field (name "MANUFACTURER PART NUMBER") "TNPW120682K0BEEA")
        (field (name "CREATED FROM") "TGaupp")
      )
      (libsource (lib "user") (part "Resistor"))
    )
    (comp (ref "R30")
      (value "82k")
      (footprint "RES 1206_3216")
      (description "SMD resistor 82Kohms .1% 25ppm")
      (fields
        (field (name "MANUFACTURER") "Vishay")
        (field (name "MANUFACTURER PART NUMBER") "TNPW120682K0BEEA")
        (field (name "CREATED FROM") "TGaupp")
      )
      (libsource (lib "user") (part "Resistor"))
    )
    (comp (ref "R31")
      (value "82k")
      (footprint "RES 1206_3216")
      (description "SMD resistor 82Kohms .1% 25ppm")
      (fields
        (field (name "MANUFACTURER") "Vishay")
        (field (name "MANUFACTURER PART NUMBER") "TNPW120682K0BEEA")
        (field (name "CREATED FROM") "TGaupp")
      )
      (libsource (lib "user") (part "Resistor"))
    )
    (comp (ref "R32")
      (value "82k")
      (footprint "RES 1206_3216")
      (description "SMD resistor 82Kohms .1% 25ppm")
      (fields
        (field (name "MANUFACTURER") "Vishay")
        (field (name "MANUFACTURER PART NUMBER") "TNPW120682K0BEEA")
        (field (name "CREATED FROM") "TGaupp")
      )
      (libsource (lib "user") (part "Resistor"))
    )
    (comp (ref "R33")
      (value "82k")
      (footprint "RES 1206_3216")
      (description "SMD resistor 82Kohms .1% 25ppm")
      (fields
        (field (name "MANUFACTURER") "Vishay")
        (field (name "MANUFACTURER PART NUMBER") "TNPW120682K0BEEA")
        (field (name "CREATED FROM") "TGaupp")
      )
      (libsource (lib "user") (part "Resistor"))
    )
    (comp (ref "R34")
      (value "82k")
      (footprint "RES 1206_3216")
      (description "SMD resistor 82Kohms .1% 25ppm")
      (fields
        (field (name "MANUFACTURER") "Vishay")
        (field (name "MANUFACTURER PART NUMBER") "TNPW120682K0BEEA")
        (field (name "CREATED FROM") "TGaupp")
      )
      (libsource (lib "user") (part "Resistor"))
    )
    (comp (ref "R35")
      (value "82k")
      (footprint "RES 1206_3216")
      (description "SMD resistor 82Kohms .1% 25ppm")
      (fields
        (field (name "MANUFACTURER") "Vishay")
        (field (name "MANUFACTURER PART NUMBER") "TNPW120682K0BEEA")
        (field (name "CREATED FROM") "TGaupp")
      )
      (libsource (lib "user") (part "Resistor"))
    )
    (comp (ref "R36")
      (value "82k")
      (footprint "RES 1206_3216")
      (description "SMD resistor 82Kohms .1% 25ppm")
      (fields
        (field (name "MANUFACTURER") "Vishay")
        (field (name "MANUFACTURER PART NUMBER") "TNPW120682K0BEEA")
        (field (name "CREATED FROM") "TGaupp")
      )
      (libsource (lib "user") (part "Resistor"))
    )
    (comp (ref "R37")
      (value "82k")
      (footprint "RES 1206_3216")
      (description "SMD resistor 82Kohms .1% 25ppm")
      (fields
        (field (name "MANUFACTURER") "Vishay")
        (field (name "MANUFACTURER PART NUMBER") "TNPW120682K0BEEA")
        (field (name "CREATED FROM") "TGaupp")
      )
      (libsource (lib "user") (part "Resistor"))
    )
    (comp (ref "R38")
      (value "82k")
      (footprint "RES 1206_3216")
      (description "SMD resistor 82Kohms .1% 25ppm")
      (fields
        (field (name "MANUFACTURER") "Vishay")
        (field (name "MANUFACTURER PART NUMBER") "TNPW120682K0BEEA")
        (field (name "CREATED FROM") "TGaupp")
      )
      (libsource (lib "user") (part "Resistor"))
    )
    (comp (ref "R39")
      (value "82k")
      (footprint "RES 1206_3216")
      (description "SMD resistor 82Kohms .1% 25ppm")
      (fields
        (field (name "MANUFACTURER") "Vishay")
        (field (name "MANUFACTURER PART NUMBER") "TNPW120682K0BEEA")
        (field (name "CREATED FROM") "TGaupp")
      )
      (libsource (lib "user") (part "Resistor"))
    )
    (comp (ref "R40")
      (value "82k")
      (footprint "RES 1206_3216")
      (description "SMD resistor 82Kohms .1% 25ppm")
      (fields
        (field (name "MANUFACTURER") "Vishay")
        (field (name "MANUFACTURER PART NUMBER") "TNPW120682K0BEEA")
        (field (name "CREATED FROM") "TGaupp")
      )
      (libsource (lib "user") (part "Resistor"))
    )
    (comp (ref "R41")
      (value "10R")
      (footprint "RES 0603_1608")
      (description "SMD 1/10watt 10ohms 1%")
      (fields
        (field (name "MANUFACTURER PART NUMBER") "CRCW060310R0FKTA")
        (field (name "MANUFACTURER") "Vishay")
        (field (name "CREATED FROM") "TGaupp")
      )
      (libsource (lib "user") (part "Resistor"))
    )
    (comp (ref "R42")
      (value "82R")
      (footprint "RES 1206_3216")
      (description "SMD resistor 1/4W 82 ohm .1% 25ppm")
      (fields
        (field (name "MANUFACTURER") "YAGEO")
        (field (name "MANUFACTURER PART NUMBER") "RT1206BRD0782RL")
        (field (name "CREATED FROM") "TGaupp")
      )
      (libsource (lib "user") (part "Resistor"))
    )
    (comp (ref "R43")
      (value "82k")
      (footprint "RES 1206_3216")
      (description "SMD resistor 82Kohms .1% 25ppm")
      (fields
        (field (name "MANUFACTURER") "Vishay")
        (field (name "MANUFACTURER PART NUMBER") "TNPW120682K0BEEA")
        (field (name "CREATED FROM") "TGaupp")
      )
      (libsource (lib "user") (part "Resistor"))
    )
    (comp (ref "R44")
      (value "82k")
      (footprint "RES 1206_3216")
      (description "SMD resistor 82Kohms .1% 25ppm")
      (fields
        (field (name "MANUFACTURER") "Vishay")
        (field (name "MANUFACTURER PART NUMBER") "TNPW120682K0BEEA")
        (field (name "CREATED FROM") "TGaupp")
      )
      (libsource (lib "user") (part "Resistor"))
    )
    (comp (ref "R45")
      (value "82k")
      (footprint "RES 1206_3216")
      (description "SMD resistor 82Kohms .1% 25ppm")
      (fields
        (field (name "MANUFACTURER") "Vishay")
        (field (name "MANUFACTURER PART NUMBER") "TNPW120682K0BEEA")
        (field (name "CREATED FROM") "TGaupp")
      )
      (libsource (lib "user") (part "Resistor"))
    )
    (comp (ref "R46")
      (value "82k")
      (footprint "RES 1206_3216")
      (description "SMD resistor 82Kohms .1% 25ppm")
      (fields
        (field (name "MANUFACTURER") "Vishay")
        (field (name "MANUFACTURER PART NUMBER") "TNPW120682K0BEEA")
        (field (name "CREATED FROM") "TGaupp")
      )
      (libsource (lib "user") (part "Resistor"))
    )
    (comp (ref "R47")
      (value "82k")
      (footprint "RES 1206_3216")
      (description "SMD resistor 82Kohms .1% 25ppm")
      (fields
        (field (name "MANUFACTURER") "Vishay")
        (field (name "MANUFACTURER PART NUMBER") "TNPW120682K0BEEA")
        (field (name "CREATED FROM") "TGaupp")
      )
      (libsource (lib "user") (part "Resistor"))
    )
    (comp (ref "R48")
      (value "82k")
      (footprint "RES 1206_3216")
      (description "SMD resistor 82Kohms .1% 25ppm")
      (fields
        (field (name "MANUFACTURER") "Vishay")
        (field (name "MANUFACTURER PART NUMBER") "TNPW120682K0BEEA")
        (field (name "CREATED FROM") "TGaupp")
      )
      (libsource (lib "user") (part "Resistor"))
    )
    (comp (ref "R49")
      (value "82k")
      (footprint "RES 1206_3216")
      (description "SMD resistor 82Kohms .1% 25ppm")
      (fields
        (field (name "MANUFACTURER") "Vishay")
        (field (name "MANUFACTURER PART NUMBER") "TNPW120682K0BEEA")
        (field (name "CREATED FROM") "TGaupp")
      )
      (libsource (lib "user") (part "Resistor"))
    )
    (comp (ref "R50")
      (value "82k")
      (footprint "RES 1206_3216")
      (description "SMD resistor 82Kohms .1% 25ppm")
      (fields
        (field (name "MANUFACTURER") "Vishay")
        (field (name "MANUFACTURER PART NUMBER") "TNPW120682K0BEEA")
        (field (name "CREATED FROM") "TGaupp")
      )
      (libsource (lib "user") (part "Resistor"))
    )
    (comp (ref "R51")
      (value "82k")
      (footprint "RES 1206_3216")
      (description "SMD resistor 82Kohms .1% 25ppm")
      (fields
        (field (name "MANUFACTURER") "Vishay")
        (field (name "MANUFACTURER PART NUMBER") "TNPW120682K0BEEA")
        (field (name "CREATED FROM") "TGaupp")
      )
      (libsource (lib "user") (part "Resistor"))
    )
    (comp (ref "R52")
      (value "82k")
      (footprint "RES 1206_3216")
      (description "SMD resistor 82Kohms .1% 25ppm")
      (fields
        (field (name "MANUFACTURER") "Vishay")
        (field (name "MANUFACTURER PART NUMBER") "TNPW120682K0BEEA")
        (field (name "CREATED FROM") "TGaupp")
      )
      (libsource (lib "user") (part "Resistor"))
    )
    (comp (ref "R53")
      (value "82k")
      (footprint "RES 1206_3216")
      (description "SMD resistor 82Kohms .1% 25ppm")
      (fields
        (field (name "MANUFACTURER") "Vishay")
        (field (name "MANUFACTURER PART NUMBER") "TNPW120682K0BEEA")
        (field (name "CREATED FROM") "TGaupp")
      )
      (libsource (lib "user") (part "Resistor"))
    )
    (comp (ref "R54")
      (value "82k")
      (footprint "RES 1206_3216")
      (description "SMD resistor 82Kohms .1% 25ppm")
      (fields
        (field (name "MANUFACTURER") "Vishay")
        (field (name "MANUFACTURER PART NUMBER") "TNPW120682K0BEEA")
        (field (name "CREATED FROM") "TGaupp")
      )
      (libsource (lib "user") (part "Resistor"))
    )
    (comp (ref "R55")
      (value "82k")
      (footprint "RES 1206_3216")
      (description "SMD resistor 82Kohms .1% 25ppm")
      (fields
        (field (name "MANUFACTURER") "Vishay")
        (field (name "MANUFACTURER PART NUMBER") "TNPW120682K0BEEA")
        (field (name "CREATED FROM") "TGaupp")
      )
      (libsource (lib "user") (part "Resistor"))
    )
    (comp (ref "R56")
      (value "82k")
      (footprint "RES 1206_3216")
      (description "SMD resistor 82Kohms .1% 25ppm")
      (fields
        (field (name "MANUFACTURER") "Vishay")
        (field (name "MANUFACTURER PART NUMBER") "TNPW120682K0BEEA")
        (field (name "CREATED FROM") "TGaupp")
      )
      (libsource (lib "user") (part "Resistor"))
    )
    (comp (ref "R57")
      (value "82k")
      (footprint "RES 1206_3216")
      (description "SMD resistor 82Kohms .1% 25ppm")
      (fields
        (field (name "MANUFACTURER") "Vishay")
        (field (name "MANUFACTURER PART NUMBER") "TNPW120682K0BEEA")
        (field (name "CREATED FROM") "TGaupp")
      )
      (libsource (lib "user") (part "Resistor"))
    )
    (comp (ref "R58")
      (value "82k")
      (footprint "RES 1206_3216")
      (description "SMD resistor 82Kohms .1% 25ppm")
      (fields
        (field (name "MANUFACTURER") "Vishay")
        (field (name "MANUFACTURER PART NUMBER") "TNPW120682K0BEEA")
        (field (name "CREATED FROM") "TGaupp")
      )
      (libsource (lib "user") (part "Resistor"))
    )
    (comp (ref "R59")
      (value "82k")
      (footprint "RES 1206_3216")
      (description "SMD resistor 82Kohms .1% 25ppm")
      (fields
        (field (name "MANUFACTURER") "Vishay")
        (field (name "MANUFACTURER PART NUMBER") "TNPW120682K0BEEA")
        (field (name "CREATED FROM") "TGaupp")
      )
      (libsource (lib "user") (part "Resistor"))
    )
    (comp (ref "R60")
      (value "82k")
      (footprint "RES 1206_3216")
      (description "SMD resistor 82Kohms .1% 25ppm")
      (fields
        (field (name "MANUFACTURER") "Vishay")
        (field (name "MANUFACTURER PART NUMBER") "TNPW120682K0BEEA")
        (field (name "CREATED FROM") "TGaupp")
      )
      (libsource (lib "user") (part "Resistor"))
    )
    (comp (ref "R61")
      (value "82k")
      (footprint "RES 1206_3216")
      (description "SMD resistor 82Kohms .1% 25ppm")
      (fields
        (field (name "MANUFACTURER") "Vishay")
        (field (name "MANUFACTURER PART NUMBER") "TNPW120682K0BEEA")
        (field (name "CREATED FROM") "TGaupp")
      )
      (libsource (lib "user") (part "Resistor"))
    )
    (comp (ref "R62")
      (value "82k")
      (footprint "RES 1206_3216")
      (description "SMD resistor 82Kohms .1% 25ppm")
      (fields
        (field (name "MANUFACTURER") "Vishay")
        (field (name "MANUFACTURER PART NUMBER") "TNPW120682K0BEEA")
        (field (name "CREATED FROM") "TGaupp")
      )
      (libsource (lib "user") (part "Resistor"))
    )
    (comp (ref "R63")
      (value "82k")
      (footprint "RES 1206_3216")
      (description "SMD resistor 82Kohms .1% 25ppm")
      (fields
        (field (name "MANUFACTURER") "Vishay")
        (field (name "MANUFACTURER PART NUMBER") "TNPW120682K0BEEA")
        (field (name "CREATED FROM") "TGaupp")
      )
      (libsource (lib "user") (part "Resistor"))
    )
    (comp (ref "R64")
      (value "82k")
      (footprint "RES 1206_3216")
      (description "SMD resistor 82Kohms .1% 25ppm")
      (fields
        (field (name "MANUFACTURER") "Vishay")
        (field (name "MANUFACTURER PART NUMBER") "TNPW120682K0BEEA")
        (field (name "CREATED FROM") "TGaupp")
      )
      (libsource (lib "user") (part "Resistor"))
    )
    (comp (ref "R65")
      (value "82k")
      (footprint "RES 1206_3216")
      (description "SMD resistor 82Kohms .1% 25ppm")
      (fields
        (field (name "MANUFACTURER") "Vishay")
        (field (name "MANUFACTURER PART NUMBER") "TNPW120682K0BEEA")
        (field (name "CREATED FROM") "TGaupp")
      )
      (libsource (lib "user") (part "Resistor"))
    )
    (comp (ref "R66")
      (value "82k")
      (footprint "RES 1206_3216")
      (description "SMD resistor 82Kohms .1% 25ppm")
      (fields
        (field (name "MANUFACTURER") "Vishay")
        (field (name "MANUFACTURER PART NUMBER") "TNPW120682K0BEEA")
        (field (name "CREATED FROM") "TGaupp")
      )
      (libsource (lib "user") (part "Resistor"))
    )
    (comp (ref "R67")
      (value "82k")
      (footprint "RES 1206_3216")
      (description "SMD resistor 82Kohms .1% 25ppm")
      (fields
        (field (name "MANUFACTURER") "Vishay")
        (field (name "MANUFACTURER PART NUMBER") "TNPW120682K0BEEA")
        (field (name "CREATED FROM") "TGaupp")
      )
      (libsource (lib "user") (part "Resistor"))
    )
    (comp (ref "R68")
      (value "82k")
      (footprint "RES 1206_3216")
      (description "SMD resistor 82Kohms .1% 25ppm")
      (fields
        (field (name "MANUFACTURER") "Vishay")
        (field (name "MANUFACTURER PART NUMBER") "TNPW120682K0BEEA")
        (field (name "CREATED FROM") "TGaupp")
      )
      (libsource (lib "user") (part "Resistor"))
    )
    (comp (ref "R69")
      (value "82k")
      (footprint "RES 1206_3216")
      (description "SMD resistor 82Kohms .1% 25ppm")
      (fields
        (field (name "MANUFACTURER") "Vishay")
        (field (name "MANUFACTURER PART NUMBER") "TNPW120682K0BEEA")
        (field (name "CREATED FROM") "TGaupp")
      )
      (libsource (lib "user") (part "Resistor"))
    )
    (comp (ref "R70")
      (value "82k")
      (footprint "RES 1206_3216")
      (description "SMD resistor 82Kohms .1% 25ppm")
      (fields
        (field (name "MANUFACTURER") "Vishay")
        (field (name "MANUFACTURER PART NUMBER") "TNPW120682K0BEEA")
        (field (name "CREATED FROM") "TGaupp")
      )
      (libsource (lib "user") (part "Resistor"))
    )
    (comp (ref "R71")
      (value "82k")
      (footprint "RES 1206_3216")
      (description "SMD resistor 82Kohms .1% 25ppm")
      (fields
        (field (name "MANUFACTURER") "Vishay")
        (field (name "MANUFACTURER PART NUMBER") "TNPW120682K0BEEA")
        (field (name "CREATED FROM") "TGaupp")
      )
      (libsource (lib "user") (part "Resistor"))
    )
    (comp (ref "R72")
      (value "82k")
      (footprint "RES 1206_3216")
      (description "SMD resistor 82Kohms .1% 25ppm")
      (fields
        (field (name "MANUFACTURER") "Vishay")
        (field (name "MANUFACTURER PART NUMBER") "TNPW120682K0BEEA")
        (field (name "CREATED FROM") "TGaupp")
      )
      (libsource (lib "user") (part "Resistor"))
    )
    (comp (ref "R73")
      (value "82k")
      (footprint "RES 1206_3216")
      (description "SMD resistor 82Kohms .1% 25ppm")
      (fields
        (field (name "MANUFACTURER") "Vishay")
        (field (name "MANUFACTURER PART NUMBER") "TNPW120682K0BEEA")
        (field (name "CREATED FROM") "TGaupp")
      )
      (libsource (lib "user") (part "Resistor"))
    )
    (comp (ref "R74")
      (value "82k")
      (footprint "RES 1206_3216")
      (description "SMD resistor 82Kohms .1% 25ppm")
      (fields
        (field (name "MANUFACTURER") "Vishay")
        (field (name "MANUFACTURER PART NUMBER") "TNPW120682K0BEEA")
        (field (name "CREATED FROM") "TGaupp")
      )
      (libsource (lib "user") (part "Resistor"))
    )
    (comp (ref "R75")
      (value "82k")
      (footprint "RES 1206_3216")
      (description "SMD resistor 82Kohms .1% 25ppm")
      (fields
        (field (name "MANUFACTURER") "Vishay")
        (field (name "MANUFACTURER PART NUMBER") "TNPW120682K0BEEA")
        (field (name "CREATED FROM") "TGaupp")
      )
      (libsource (lib "user") (part "Resistor"))
    )
    (comp (ref "R76")
      (value "82k")
      (footprint "RES 1206_3216")
      (description "SMD resistor 82Kohms .1% 25ppm")
      (fields
        (field (name "MANUFACTURER") "Vishay")
        (field (name "MANUFACTURER PART NUMBER") "TNPW120682K0BEEA")
        (field (name "CREATED FROM") "TGaupp")
      )
      (libsource (lib "user") (part "Resistor"))
    )
    (comp (ref "R77")
      (value "82k")
      (footprint "RES 1206_3216")
      (description "SMD resistor 82Kohms .1% 25ppm")
      (fields
        (field (name "MANUFACTURER") "Vishay")
        (field (name "MANUFACTURER PART NUMBER") "TNPW120682K0BEEA")
        (field (name "CREATED FROM") "TGaupp")
      )
      (libsource (lib "user") (part "Resistor"))
    )
  )
  (nets
    (net (code "1") (name "/U_IN_P") (class "Default")
      (node (ref "C13") (pin "1") (pinfunction "1_1") (pintype "passive"))
      (node (ref "R1") (pin "1") (pinfunction "1_1") (pintype "passive"))
    )
    (net (code "2") (name "/U_Zwischen_P") (class "Default")
      (node (ref "C54") (pin "2") (pinfunction "2_2") (pintype "passive"))
      (node (ref "R41") (pin "2") (pinfunction "2_2") (pintype "passive"))
    )
    (net (code "3") (name "GND_HV") (class "Default")
      (node (ref "C53") (pin "1") (pinfunction "1_1") (pintype "passive"))
      (node (ref "C54") (pin "1") (pinfunction "1_1") (pintype "passive"))
      (node (ref "R42") (pin "1") (pinfunction "1_1") (pintype "passive"))
    )
    (net (code "4") (name "Net-(C13-Pad2)") (class "Default")
      (node (ref "C13") (pin "2") (pinfunction "2_2") (pintype "passive"))
      (node (ref "C14") (pin "1") (pinfunction "1_1") (pintype "passive"))
      (node (ref "R1") (pin "2") (pinfunction "2_2") (pintype "passive"))
      (node (ref "R2") (pin "1") (pinfunction "1_1") (pintype "passive"))
    )
    (net (code "5") (name "Net-(C14-Pad2)") (class "Default")
      (node (ref "C14") (pin "2") (pinfunction "2_2") (pintype "passive"))
      (node (ref "C15") (pin "1") (pinfunction "1_1") (pintype "passive"))
      (node (ref "R2") (pin "2") (pinfunction "2_2") (pintype "passive"))
      (node (ref "R3") (pin "1") (pinfunction "1_1") (pintype "passive"))
    )
    (net (code "6") (name "Net-(C15-Pad2)") (class "Default")
      (node (ref "C15") (pin "2") (pinfunction "2_2") (pintype "passive"))
      (node (ref "C16") (pin "1") (pinfunction "1_1") (pintype "passive"))
      (node (ref "R3") (pin "2") (pinfunction "2_2") (pintype "passive"))
      (node (ref "R4") (pin "1") (pinfunction "1_1") (pintype "passive"))
    )
    (net (code "7") (name "Net-(C16-Pad2)") (class "Default")
      (node (ref "C16") (pin "2") (pinfunction "2_2") (pintype "passive"))
      (node (ref "C17") (pin "1") (pinfunction "1_1") (pintype "passive"))
      (node (ref "R4") (pin "2") (pinfunction "2_2") (pintype "passive"))
      (node (ref "R5") (pin "1") (pinfunction "1_1") (pintype "passive"))
    )
    (net (code "8") (name "Net-(C17-Pad2)") (class "Default")
      (node (ref "C17") (pin "2") (pinfunction "2_2") (pintype "passive"))
      (node (ref "C18") (pin "1") (pinfunction "1_1") (pintype "passive"))
      (node (ref "R5") (pin "2") (pinfunction "2_2") (pintype "passive"))
      (node (ref "R6") (pin "1") (pinfunction "1_1") (pintype "passive"))
    )
    (net (code "9") (name "Net-(C18-Pad2)") (class "Default")
      (node (ref "C18") (pin "2") (pinfunction "2_2") (pintype "passive"))
      (node (ref "C19") (pin "1") (pinfunction "1_1") (pintype "passive"))
      (node (ref "R6") (pin "2") (pinfunction "2_2") (pintype "passive"))
      (node (ref "R7") (pin "1") (pinfunction "1_1") (pintype "passive"))
    )
    (net (code "10") (name "Net-(C19-Pad2)") (class "Default")
      (node (ref "C19") (pin "2") (pinfunction "2_2") (pintype "passive"))
      (node (ref "C20") (pin "1") (pinfunction "1_1") (pintype "passive"))
      (node (ref "R7") (pin "2") (pinfunction "2_2") (pintype "passive"))
      (node (ref "R8") (pin "1") (pinfunction "1_1") (pintype "passive"))
    )
    (net (code "11") (name "Net-(C20-Pad2)") (class "Default")
      (node (ref "C20") (pin "2") (pinfunction "2_2") (pintype "passive"))
      (node (ref "C21") (pin "1") (pinfunction "1_1") (pintype "passive"))
      (node (ref "R8") (pin "2") (pinfunction "2_2") (pintype "passive"))
      (node (ref "R9") (pin "1") (pinfunction "1_1") (pintype "passive"))
    )
    (net (code "12") (name "Net-(C21-Pad2)") (class "Default")
      (node (ref "C21") (pin "2") (pinfunction "2_2") (pintype "passive"))
      (node (ref "C22") (pin "1") (pinfunction "1_1") (pintype "passive"))
      (node (ref "R10") (pin "1") (pinfunction "1_1") (pintype "passive"))
      (node (ref "R9") (pin "2") (pinfunction "2_2") (pintype "passive"))
    )
    (net (code "13") (name "Net-(C22-Pad2)") (class "Default")
      (node (ref "C22") (pin "2") (pinfunction "2_2") (pintype "passive"))
      (node (ref "C23") (pin "1") (pinfunction "1_1") (pintype "passive"))
      (node (ref "R10") (pin "2") (pinfunction "2_2") (pintype "passive"))
      (node (ref "R11") (pin "1") (pinfunction "1_1") (pintype "passive"))
    )
    (net (code "14") (name "Net-(C23-Pad2)") (class "Default")
      (node (ref "C23") (pin "2") (pinfunction "2_2") (pintype "passive"))
      (node (ref "C24") (pin "1") (pinfunction "1_1") (pintype "passive"))
      (node (ref "R11") (pin "2") (pinfunction "2_2") (pintype "passive"))
      (node (ref "R12") (pin "1") (pinfunction "1_1") (pintype "passive"))
    )
    (net (code "15") (name "Net-(C24-Pad2)") (class "Default")
      (node (ref "C24") (pin "2") (pinfunction "2_2") (pintype "passive"))
      (node (ref "C25") (pin "1") (pinfunction "1_1") (pintype "passive"))
      (node (ref "R12") (pin "2") (pinfunction "2_2") (pintype "passive"))
      (node (ref "R13") (pin "1") (pinfunction "1_1") (pintype "passive"))
    )
    (net (code "16") (name "Net-(C25-Pad2)") (class "Default")
      (node (ref "C25") (pin "2") (pinfunction "2_2") (pintype "passive"))
      (node (ref "C26") (pin "1") (pinfunction "1_1") (pintype "passive"))
      (node (ref "R13") (pin "2") (pinfunction "2_2") (pintype "passive"))
      (node (ref "R14") (pin "1") (pinfunction "1_1") (pintype "passive"))
    )
    (net (code "17") (name "Net-(C26-Pad2)") (class "Default")
      (node (ref "C26") (pin "2") (pinfunction "2_2") (pintype "passive"))
      (node (ref "C27") (pin "1") (pinfunction "1_1") (pintype "passive"))
      (node (ref "R14") (pin "2") (pinfunction "2_2") (pintype "passive"))
      (node (ref "R15") (pin "1") (pinfunction "1_1") (pintype "passive"))
    )
    (net (code "18") (name "Net-(C27-Pad2)") (class "Default")
      (node (ref "C27") (pin "2") (pinfunction "2_2") (pintype "passive"))
      (node (ref "C28") (pin "1") (pinfunction "1_1") (pintype "passive"))
      (node (ref "R15") (pin "2") (pinfunction "2_2") (pintype "passive"))
      (node (ref "R16") (pin "1") (pinfunction "1_1") (pintype "passive"))
    )
    (net (code "19") (name "Net-(C28-Pad2)") (class "Default")
      (node (ref "C28") (pin "2") (pinfunction "2_2") (pintype "passive"))
      (node (ref "C29") (pin "1") (pinfunction "1_1") (pintype "passive"))
      (node (ref "R16") (pin "2") (pinfunction "2_2") (pintype "passive"))
      (node (ref "R17") (pin "1") (pinfunction "1_1") (pintype "passive"))
    )
    (net (code "20") (name "Net-(C29-Pad2)") (class "Default")
      (node (ref "C29") (pin "2") (pinfunction "2_2") (pintype "passive"))
      (node (ref "C30") (pin "1") (pinfunction "1_1") (pintype "passive"))
      (node (ref "R17") (pin "2") (pinfunction "2_2") (pintype "passive"))
      (node (ref "R18") (pin "1") (pinfunction "1_1") (pintype "passive"))
    )
    (net (code "21") (name "Net-(C30-Pad2)") (class "Default")
      (node (ref "C30") (pin "2") (pinfunction "2_2") (pintype "passive"))
      (node (ref "C31") (pin "1") (pinfunction "1_1") (pintype "passive"))
      (node (ref "R18") (pin "2") (pinfunction "2_2") (pintype "passive"))
      (node (ref "R19") (pin "1") (pinfunction "1_1") (pintype "passive"))
    )
    (net (code "22") (name "Net-(C31-Pad2)") (class "Default")
      (node (ref "C31") (pin "2") (pinfunction "2_2") (pintype "passive"))
      (node (ref "C32") (pin "1") (pinfunction "1_1") (pintype "passive"))
      (node (ref "R19") (pin "2") (pinfunction "2_2") (pintype "passive"))
      (node (ref "R20") (pin "1") (pinfunction "1_1") (pintype "passive"))
    )
    (net (code "23") (name "Net-(C32-Pad2)") (class "Default")
      (node (ref "C32") (pin "2") (pinfunction "2_2") (pintype "passive"))
      (node (ref "C33") (pin "1") (pinfunction "1_1") (pintype "passive"))
      (node (ref "R20") (pin "2") (pinfunction "2_2") (pintype "passive"))
      (node (ref "R21") (pin "1") (pinfunction "1_1") (pintype "passive"))
    )
    (net (code "24") (name "Net-(C33-Pad2)") (class "Default")
      (node (ref "C33") (pin "2") (pinfunction "2_2") (pintype "passive"))
      (node (ref "C34") (pin "1") (pinfunction "1_1") (pintype "passive"))
      (node (ref "R21") (pin "2") (pinfunction "2_2") (pintype "passive"))
      (node (ref "R22") (pin "1") (pinfunction "1_1") (pintype "passive"))
    )
    (net (code "25") (name "Net-(C34-Pad2)") (class "Default")
      (node (ref "C34") (pin "2") (pinfunction "2_2") (pintype "passive"))
      (node (ref "C35") (pin "1") (pinfunction "1_1") (pintype "passive"))
      (node (ref "R22") (pin "2") (pinfunction "2_2") (pintype "passive"))
      (node (ref "R23") (pin "1") (pinfunction "1_1") (pintype "passive"))
    )
    (net (code "26") (name "Net-(C35-Pad2)") (class "Default")
      (node (ref "C35") (pin "2") (pinfunction "2_2") (pintype "passive"))
      (node (ref "C36") (pin "1") (pinfunction "1_1") (pintype "passive"))
      (node (ref "R23") (pin "2") (pinfunction "2_2") (pintype "passive"))
      (node (ref "R24") (pin "1") (pinfunction "1_1") (pintype "passive"))
    )
    (net (code "27") (name "Net-(C36-Pad2)") (class "Default")
      (node (ref "C36") (pin "2") (pinfunction "2_2") (pintype "passive"))
      (node (ref "C37") (pin "1") (pinfunction "1_1") (pintype "passive"))
      (node (ref "R24") (pin "2") (pinfunction "2_2") (pintype "passive"))
      (node (ref "R25") (pin "1") (pinfunction "1_1") (pintype "passive"))
    )
    (net (code "28") (name "Net-(C37-Pad2)") (class "Default")
      (node (ref "C37") (pin "2") (pinfunction "2_2") (pintype "passive"))
      (node (ref "C38") (pin "1") (pinfunction "1_1") (pintype "passive"))
      (node (ref "R25") (pin "2") (pinfunction "2_2") (pintype "passive"))
      (node (ref "R26") (pin "1") (pinfunction "1_1") (pintype "passive"))
    )
    (net (code "29") (name "Net-(C38-Pad2)") (class "Default")
      (node (ref "C38") (pin "2") (pinfunction "2_2") (pintype "passive"))
      (node (ref "C39") (pin "1") (pinfunction "1_1") (pintype "passive"))
      (node (ref "R26") (pin "2") (pinfunction "2_2") (pintype "passive"))
      (node (ref "R27") (pin "1") (pinfunction "1_1") (pintype "passive"))
    )
    (net (code "30") (name "Net-(C39-Pad2)") (class "Default")
      (node (ref "C39") (pin "2") (pinfunction "2_2") (pintype "passive"))
      (node (ref "C40") (pin "1") (pinfunction "1_1") (pintype "passive"))
      (node (ref "R27") (pin "2") (pinfunction "2_2") (pintype "passive"))
      (node (ref "R28") (pin "1") (pinfunction "1_1") (pintype "passive"))
    )
    (net (code "31") (name "Net-(C40-Pad2)") (class "Default")
      (node (ref "C40") (pin "2") (pinfunction "2_2") (pintype "passive"))
      (node (ref "C41") (pin "1") (pinfunction "1_1") (pintype "passive"))
      (node (ref "R28") (pin "2") (pinfunction "2_2") (pintype "passive"))
      (node (ref "R29") (pin "1") (pinfunction "1_1") (pintype "passive"))
    )
    (net (code "32") (name "Net-(C41-Pad2)") (class "Default")
      (node (ref "C41") (pin "2") (pinfunction "2_2") (pintype "passive"))
      (node (ref "C42") (pin "1") (pinfunction "1_1") (pintype "passive"))
      (node (ref "R29") (pin "2") (pinfunction "2_2") (pintype "passive"))
      (node (ref "R30") (pin "1") (pinfunction "1_1") (pintype "passive"))
    )
    (net (code "33") (name "Net-(C42-Pad2)") (class "Default")
      (node (ref "C42") (pin "2") (pinfunction "2_2") (pintype "passive"))
      (node (ref "C43") (pin "1") (pinfunction "1_1") (pintype "passive"))
      (node (ref "R30") (pin "2") (pinfunction "2_2") (pintype "passive"))
      (node (ref "R31") (pin "1") (pinfunction "1_1") (pintype "passive"))
    )
    (net (code "34") (name "Net-(C43-Pad2)") (class "Default")
      (node (ref "C43") (pin "2") (pinfunction "2_2") (pintype "passive"))
      (node (ref "C44") (pin "1") (pinfunction "1_1") (pintype "passive"))
      (node (ref "R31") (pin "2") (pinfunction "2_2") (pintype "passive"))
      (node (ref "R32") (pin "1") (pinfunction "1_1") (pintype "passive"))
    )
    (net (code "35") (name "Net-(C44-Pad2)") (class "Default")
      (node (ref "C44") (pin "2") (pinfunction "2_2") (pintype "passive"))
      (node (ref "C45") (pin "1") (pinfunction "1_1") (pintype "passive"))
      (node (ref "R32") (pin "2") (pinfunction "2_2") (pintype "passive"))
      (node (ref "R33") (pin "1") (pinfunction "1_1") (pintype "passive"))
    )
    (net (code "36") (name "Net-(C45-Pad2)") (class "Default")
      (node (ref "C45") (pin "2") (pinfunction "2_2") (pintype "passive"))
      (node (ref "C46") (pin "1") (pinfunction "1_1") (pintype "passive"))
      (node (ref "R33") (pin "2") (pinfunction "2_2") (pintype "passive"))
      (node (ref "R34") (pin "1") (pinfunction "1_1") (pintype "passive"))
    )
    (net (code "37") (name "Net-(C46-Pad2)") (class "Default")
      (node (ref "C46") (pin "2") (pinfunction "2_2") (pintype "passive"))
      (node (ref "C47") (pin "1") (pinfunction "1_1") (pintype "passive"))
      (node (ref "R34") (pin "2") (pinfunction "2_2") (pintype "passive"))
      (node (ref "R35") (pin "1") (pinfunction "1_1") (pintype "passive"))
    )
    (net (code "38") (name "Net-(C47-Pad2)") (class "Default")
      (node (ref "C47") (pin "2") (pinfunction "2_2") (pintype "passive"))
      (node (ref "C48") (pin "1") (pinfunction "1_1") (pintype "passive"))
      (node (ref "R35") (pin "2") (pinfunction "2_2") (pintype "passive"))
      (node (ref "R36") (pin "1") (pinfunction "1_1") (pintype "passive"))
    )
    (net (code "39") (name "Net-(C48-Pad2)") (class "Default")
      (node (ref "C48") (pin "2") (pinfunction "2_2") (pintype "passive"))
      (node (ref "C49") (pin "1") (pinfunction "1_1") (pintype "passive"))
      (node (ref "R36") (pin "2") (pinfunction "2_2") (pintype "passive"))
      (node (ref "R37") (pin "1") (pinfunction "1_1") (pintype "passive"))
    )
    (net (code "40") (name "Net-(C49-Pad2)") (class "Default")
      (node (ref "C49") (pin "2") (pinfunction "2_2") (pintype "passive"))
      (node (ref "C50") (pin "1") (pinfunction "1_1") (pintype "passive"))
      (node (ref "R37") (pin "2") (pinfunction "2_2") (pintype "passive"))
      (node (ref "R38") (pin "1") (pinfunction "1_1") (pintype "passive"))
    )
    (net (code "41") (name "Net-(C50-Pad2)") (class "Default")
      (node (ref "C50") (pin "2") (pinfunction "2_2") (pintype "passive"))
      (node (ref "C51") (pin "1") (pinfunction "1_1") (pintype "passive"))
      (node (ref "R38") (pin "2") (pinfunction "2_2") (pintype "passive"))
      (node (ref "R39") (pin "1") (pinfunction "1_1") (pintype "passive"))
    )
    (net (code "42") (name "Net-(C51-Pad2)") (class "Default")
      (node (ref "C51") (pin "2") (pinfunction "2_2") (pintype "passive"))
      (node (ref "C52") (pin "1") (pinfunction "1_1") (pintype "passive"))
      (node (ref "R39") (pin "2") (pinfunction "2_2") (pintype "passive"))
      (node (ref "R40") (pin "1") (pinfunction "1_1") (pintype "passive"))
    )
    (net (code "43") (name "Net-(C52-Pad2)") (class "Default")
      (node (ref "C52") (pin "2") (pinfunction "2_2") (pintype "passive"))
      (node (ref "C55") (pin "1") (pinfunction "1_1") (pintype "passive"))
      (node (ref "R40") (pin "2") (pinfunction "2_2") (pintype "passive"))
      (node (ref "R43") (pin "1") (pinfunction "1_1") (pintype "passive"))
    )
    (net (code "44") (name "Net-(C53-Pad2)") (class "Default")
      (node (ref "C53") (pin "2") (pinfunction "2_2") (pintype "passive"))
      (node (ref "C89") (pin "2") (pinfunction "2_2") (pintype "passive"))
      (node (ref "R41") (pin "1") (pinfunction "1_1") (pintype "passive"))
      (node (ref "R42") (pin "2") (pinfunction "2_2") (pintype "passive"))
      (node (ref "R77") (pin "2") (pinfunction "2_2") (pintype "passive"))
    )
    (net (code "45") (name "Net-(C55-Pad2)") (class "Default")
      (node (ref "C55") (pin "2") (pinfunction "2_2") (pintype "passive"))
      (node (ref "C56") (pin "1") (pinfunction "1_1") (pintype "passive"))
      (node (ref "R43") (pin "2") (pinfunction "2_2") (pintype "passive"))
      (node (ref "R44") (pin "1") (pinfunction "1_1") (pintype "passive"))
    )
    (net (code "46") (name "Net-(C56-Pad2)") (class "Default")
      (node (ref "C56") (pin "2") (pinfunction "2_2") (pintype "passive"))
      (node (ref "C57") (pin "1") (pinfunction "1_1") (pintype "passive"))
      (node (ref "R44") (pin "2") (pinfunction "2_2") (pintype "passive"))
      (node (ref "R45") (pin "1") (pinfunction "1_1") (pintype "passive"))
    )
    (net (code "47") (name "Net-(C57-Pad2)") (class "Default")
      (node (ref "C57") (pin "2") (pinfunction "2_2") (pintype "passive"))
      (node (ref "C58") (pin "1") (pinfunction "1_1") (pintype "passive"))
      (node (ref "R45") (pin "2") (pinfunction "2_2") (pintype "passive"))
      (node (ref "R46") (pin "1") (pinfunction "1_1") (pintype "passive"))
    )
    (net (code "48") (name "Net-(C58-Pad2)") (class "Default")
      (node (ref "C58") (pin "2") (pinfunction "2_2") (pintype "passive"))
      (node (ref "C59") (pin "1") (pinfunction "1_1") (pintype "passive"))
      (node (ref "R46") (pin "2") (pinfunction "2_2") (pintype "passive"))
      (node (ref "R47") (pin "1") (pinfunction "1_1") (pintype "passive"))
    )
    (net (code "49") (name "Net-(C59-Pad2)") (class "Default")
      (node (ref "C59") (pin "2") (pinfunction "2_2") (pintype "passive"))
      (node (ref "C60") (pin "1") (pinfunction "1_1") (pintype "passive"))
      (node (ref "R47") (pin "2") (pinfunction "2_2") (pintype "passive"))
      (node (ref "R48") (pin "1") (pinfunction "1_1") (pintype "passive"))
    )
    (net (code "50") (name "Net-(C60-Pad2)") (class "Default")
      (node (ref "C60") (pin "2") (pinfunction "2_2") (pintype "passive"))
      (node (ref "C61") (pin "1") (pinfunction "1_1") (pintype "passive"))
      (node (ref "R48") (pin "2") (pinfunction "2_2") (pintype "passive"))
      (node (ref "R49") (pin "1") (pinfunction "1_1") (pintype "passive"))
    )
    (net (code "51") (name "Net-(C61-Pad2)") (class "Default")
      (node (ref "C61") (pin "2") (pinfunction "2_2") (pintype "passive"))
      (node (ref "C62") (pin "1") (pinfunction "1_1") (pintype "passive"))
      (node (ref "R49") (pin "2") (pinfunction "2_2") (pintype "passive"))
      (node (ref "R50") (pin "1") (pinfunction "1_1") (pintype "passive"))
    )
    (net (code "52") (name "Net-(C62-Pad2)") (class "Default")
      (node (ref "C62") (pin "2") (pinfunction "2_2") (pintype "passive"))
      (node (ref "C63") (pin "1") (pinfunction "1_1") (pintype "passive"))
      (node (ref "R50") (pin "2") (pinfunction "2_2") (pintype "passive"))
      (node (ref "R51") (pin "1") (pinfunction "1_1") (pintype "passive"))
    )
    (net (code "53") (name "Net-(C63-Pad2)") (class "Default")
      (node (ref "C63") (pin "2") (pinfunction "2_2") (pintype "passive"))
      (node (ref "C64") (pin "1") (pinfunction "1_1") (pintype "passive"))
      (node (ref "R51") (pin "2") (pinfunction "2_2") (pintype "passive"))
      (node (ref "R52") (pin "1") (pinfunction "1_1") (pintype "passive"))
    )
    (net (code "54") (name "Net-(C64-Pad2)") (class "Default")
      (node (ref "C64") (pin "2") (pinfunction "2_2") (pintype "passive"))
      (node (ref "C65") (pin "1") (pinfunction "1_1") (pintype "passive"))
      (node (ref "R52") (pin "2") (pinfunction "2_2") (pintype "passive"))
      (node (ref "R53") (pin "1") (pinfunction "1_1") (pintype "passive"))
    )
    (net (code "55") (name "Net-(C65-Pad2)") (class "Default")
      (node (ref "C65") (pin "2") (pinfunction "2_2") (pintype "passive"))
      (node (ref "C66") (pin "1") (pinfunction "1_1") (pintype "passive"))
      (node (ref "R53") (pin "2") (pinfunction "2_2") (pintype "passive"))
      (node (ref "R54") (pin "1") (pinfunction "1_1") (pintype "passive"))
    )
    (net (code "56") (name "Net-(C66-Pad2)") (class "Default")
      (node (ref "C66") (pin "2") (pinfunction "2_2") (pintype "passive"))
      (node (ref "C67") (pin "1") (pinfunction "1_1") (pintype "passive"))
      (node (ref "R54") (pin "2") (pinfunction "2_2") (pintype "passive"))
      (node (ref "R55") (pin "1") (pinfunction "1_1") (pintype "passive"))
    )
    (net (code "57") (name "Net-(C67-Pad2)") (class "Default")
      (node (ref "C67") (pin "2") (pinfunction "2_2") (pintype "passive"))
      (node (ref "C68") (pin "1") (pinfunction "1_1") (pintype "passive"))
      (node (ref "R55") (pin "2") (pinfunction "2_2") (pintype "passive"))
      (node (ref "R56") (pin "1") (pinfunction "1_1") (pintype "passive"))
    )
    (net (code "58") (name "Net-(C68-Pad2)") (class "Default")
      (node (ref "C68") (pin "2") (pinfunction "2_2") (pintype "passive"))
      (node (ref "C69") (pin "1") (pinfunction "1_1") (pintype "passive"))
      (node (ref "R56") (pin "2") (pinfunction "2_2") (pintype "passive"))
      (node (ref "R57") (pin "1") (pinfunction "1_1") (pintype "passive"))
    )
    (net (code "59") (name "Net-(C69-Pad2)") (class "Default")
      (node (ref "C69") (pin "2") (pinfunction "2_2") (pintype "passive"))
      (node (ref "C70") (pin "1") (pinfunction "1_1") (pintype "passive"))
      (node (ref "R57") (pin "2") (pinfunction "2_2") (pintype "passive"))
      (node (ref "R58") (pin "1") (pinfunction "1_1") (pintype "passive"))
    )
    (net (code "60") (name "Net-(C70-Pad2)") (class "Default")
      (node (ref "C70") (pin "2") (pinfunction "2_2") (pintype "passive"))
      (node (ref "C71") (pin "1") (pinfunction "1_1") (pintype "passive"))
      (node (ref "R58") (pin "2") (pinfunction "2_2") (pintype "passive"))
      (node (ref "R59") (pin "1") (pinfunction "1_1") (pintype "passive"))
    )
    (net (code "61") (name "Net-(C71-Pad2)") (class "Default")
      (node (ref "C71") (pin "2") (pinfunction "2_2") (pintype "passive"))
      (node (ref "C72") (pin "1") (pinfunction "1_1") (pintype "passive"))
      (node (ref "R59") (pin "2") (pinfunction "2_2") (pintype "passive"))
      (node (ref "R60") (pin "1") (pinfunction "1_1") (pintype "passive"))
    )
    (net (code "62") (name "Net-(C72-Pad2)") (class "Default")
      (node (ref "C72") (pin "2") (pinfunction "2_2") (pintype "passive"))
      (node (ref "C73") (pin "1") (pinfunction "1_1") (pintype "passive"))
      (node (ref "R60") (pin "2") (pinfunction "2_2") (pintype "passive"))
      (node (ref "R61") (pin "1") (pinfunction "1_1") (pintype "passive"))
    )
    (net (code "63") (name "Net-(C73-Pad2)") (class "Default")
      (node (ref "C73") (pin "2") (pinfunction "2_2") (pintype "passive"))
      (node (ref "C74") (pin "1") (pinfunction "1_1") (pintype "passive"))
      (node (ref "R61") (pin "2") (pinfunction "2_2") (pintype "passive"))
      (node (ref "R62") (pin "1") (pinfunction "1_1") (pintype "passive"))
    )
    (net (code "64") (name "Net-(C74-Pad2)") (class "Default")
      (node (ref "C74") (pin "2") (pinfunction "2_2") (pintype "passive"))
      (node (ref "C75") (pin "1") (pinfunction "1_1") (pintype "passive"))
      (node (ref "R62") (pin "2") (pinfunction "2_2") (pintype "passive"))
      (node (ref "R63") (pin "1") (pinfunction "1_1") (pintype "passive"))
    )
    (net (code "65") (name "Net-(C75-Pad2)") (class "Default")
      (node (ref "C75") (pin "2") (pinfunction "2_2") (pintype "passive"))
      (node (ref "C76") (pin "1") (pinfunction "1_1") (pintype "passive"))
      (node (ref "R63") (pin "2") (pinfunction "2_2") (pintype "passive"))
      (node (ref "R64") (pin "1") (pinfunction "1_1") (pintype "passive"))
    )
    (net (code "66") (name "Net-(C76-Pad2)") (class "Default")
      (node (ref "C76") (pin "2") (pinfunction "2_2") (pintype "passive"))
      (node (ref "C77") (pin "1") (pinfunction "1_1") (pintype "passive"))
      (node (ref "R64") (pin "2") (pinfunction "2_2") (pintype "passive"))
      (node (ref "R65") (pin "1") (pinfunction "1_1") (pintype "passive"))
    )
    (net (code "67") (name "Net-(C77-Pad2)") (class "Default")
      (node (ref "C77") (pin "2") (pinfunction "2_2") (pintype "passive"))
      (node (ref "C78") (pin "1") (pinfunction "1_1") (pintype "passive"))
      (node (ref "R65") (pin "2") (pinfunction "2_2") (pintype "passive"))
      (node (ref "R66") (pin "1") (pinfunction "1_1") (pintype "passive"))
    )
    (net (code "68") (name "Net-(C78-Pad2)") (class "Default")
      (node (ref "C78") (pin "2") (pinfunction "2_2") (pintype "passive"))
      (node (ref "C79") (pin "1") (pinfunction "1_1") (pintype "passive"))
      (node (ref "R66") (pin "2") (pinfunction "2_2") (pintype "passive"))
      (node (ref "R67") (pin "1") (pinfunction "1_1") (pintype "passive"))
    )
    (net (code "69") (name "Net-(C79-Pad2)") (class "Default")
      (node (ref "C79") (pin "2") (pinfunction "2_2") (pintype "passive"))
      (node (ref "C80") (pin "1") (pinfunction "1_1") (pintype "passive"))
      (node (ref "R67") (pin "2") (pinfunction "2_2") (pintype "passive"))
      (node (ref "R68") (pin "1") (pinfunction "1_1") (pintype "passive"))
    )
    (net (code "70") (name "Net-(C80-Pad2)") (class "Default")
      (node (ref "C80") (pin "2") (pinfunction "2_2") (pintype "passive"))
      (node (ref "C81") (pin "1") (pinfunction "1_1") (pintype "passive"))
      (node (ref "R68") (pin "2") (pinfunction "2_2") (pintype "passive"))
      (node (ref "R69") (pin "1") (pinfunction "1_1") (pintype "passive"))
    )
    (net (code "71") (name "Net-(C81-Pad2)") (class "Default")
      (node (ref "C81") (pin "2") (pinfunction "2_2") (pintype "passive"))
      (node (ref "C82") (pin "1") (pinfunction "1_1") (pintype "passive"))
      (node (ref "R69") (pin "2") (pinfunction "2_2") (pintype "passive"))
      (node (ref "R70") (pin "1") (pinfunction "1_1") (pintype "passive"))
    )
    (net (code "72") (name "Net-(C82-Pad2)") (class "Default")
      (node (ref "C82") (pin "2") (pinfunction "2_2") (pintype "passive"))
      (node (ref "C83") (pin "1") (pinfunction "1_1") (pintype "passive"))
      (node (ref "R70") (pin "2") (pinfunction "2_2") (pintype "passive"))
      (node (ref "R71") (pin "1") (pinfunction "1_1") (pintype "passive"))
    )
    (net (code "73") (name "Net-(C83-Pad2)") (class "Default")
      (node (ref "C83") (pin "2") (pinfunction "2_2") (pintype "passive"))
      (node (ref "C84") (pin "1") (pinfunction "1_1") (pintype "passive"))
      (node (ref "R71") (pin "2") (pinfunction "2_2") (pintype "passive"))
      (node (ref "R72") (pin "1") (pinfunction "1_1") (pintype "passive"))
    )
    (net (code "74") (name "Net-(C84-Pad2)") (class "Default")
      (node (ref "C84") (pin "2") (pinfunction "2_2") (pintype "passive"))
      (node (ref "C85") (pin "1") (pinfunction "1_1") (pintype "passive"))
      (node (ref "R72") (pin "2") (pinfunction "2_2") (pintype "passive"))
      (node (ref "R73") (pin "1") (pinfunction "1_1") (pintype "passive"))
    )
    (net (code "75") (name "Net-(C85-Pad2)") (class "Default")
      (node (ref "C85") (pin "2") (pinfunction "2_2") (pintype "passive"))
      (node (ref "C86") (pin "1") (pinfunction "1_1") (pintype "passive"))
      (node (ref "R73") (pin "2") (pinfunction "2_2") (pintype "passive"))
      (node (ref "R74") (pin "1") (pinfunction "1_1") (pintype "passive"))
    )
    (net (code "76") (name "Net-(C86-Pad2)") (class "Default")
      (node (ref "C86") (pin "2") (pinfunction "2_2") (pintype "passive"))
      (node (ref "C87") (pin "1") (pinfunction "1_1") (pintype "passive"))
      (node (ref "R74") (pin "2") (pinfunction "2_2") (pintype "passive"))
      (node (ref "R75") (pin "1") (pinfunction "1_1") (pintype "passive"))
    )
    (net (code "77") (name "Net-(C87-Pad2)") (class "Default")
      (node (ref "C87") (pin "2") (pinfunction "2_2") (pintype "passive"))
      (node (ref "C88") (pin "1") (pinfunction "1_1") (pintype "passive"))
      (node (ref "R75") (pin "2") (pinfunction "2_2") (pintype "passive"))
      (node (ref "R76") (pin "1") (pinfunction "1_1") (pintype "passive"))
    )
    (net (code "78") (name "Net-(C88-Pad2)") (class "Default")
      (node (ref "C88") (pin "2") (pinfunction "2_2") (pintype "passive"))
      (node (ref "C89") (pin "1") (pinfunction "1_1") (pintype "passive"))
      (node (ref "R76") (pin "2") (pinfunction "2_2") (pintype "passive"))
      (node (ref "R77") (pin "1") (pinfunction "1_1") (pintype "passive"))
    )
  )
)
